# 11-DPLL-2.net
KiCad netlist of a schematic drawn in Altium Designer
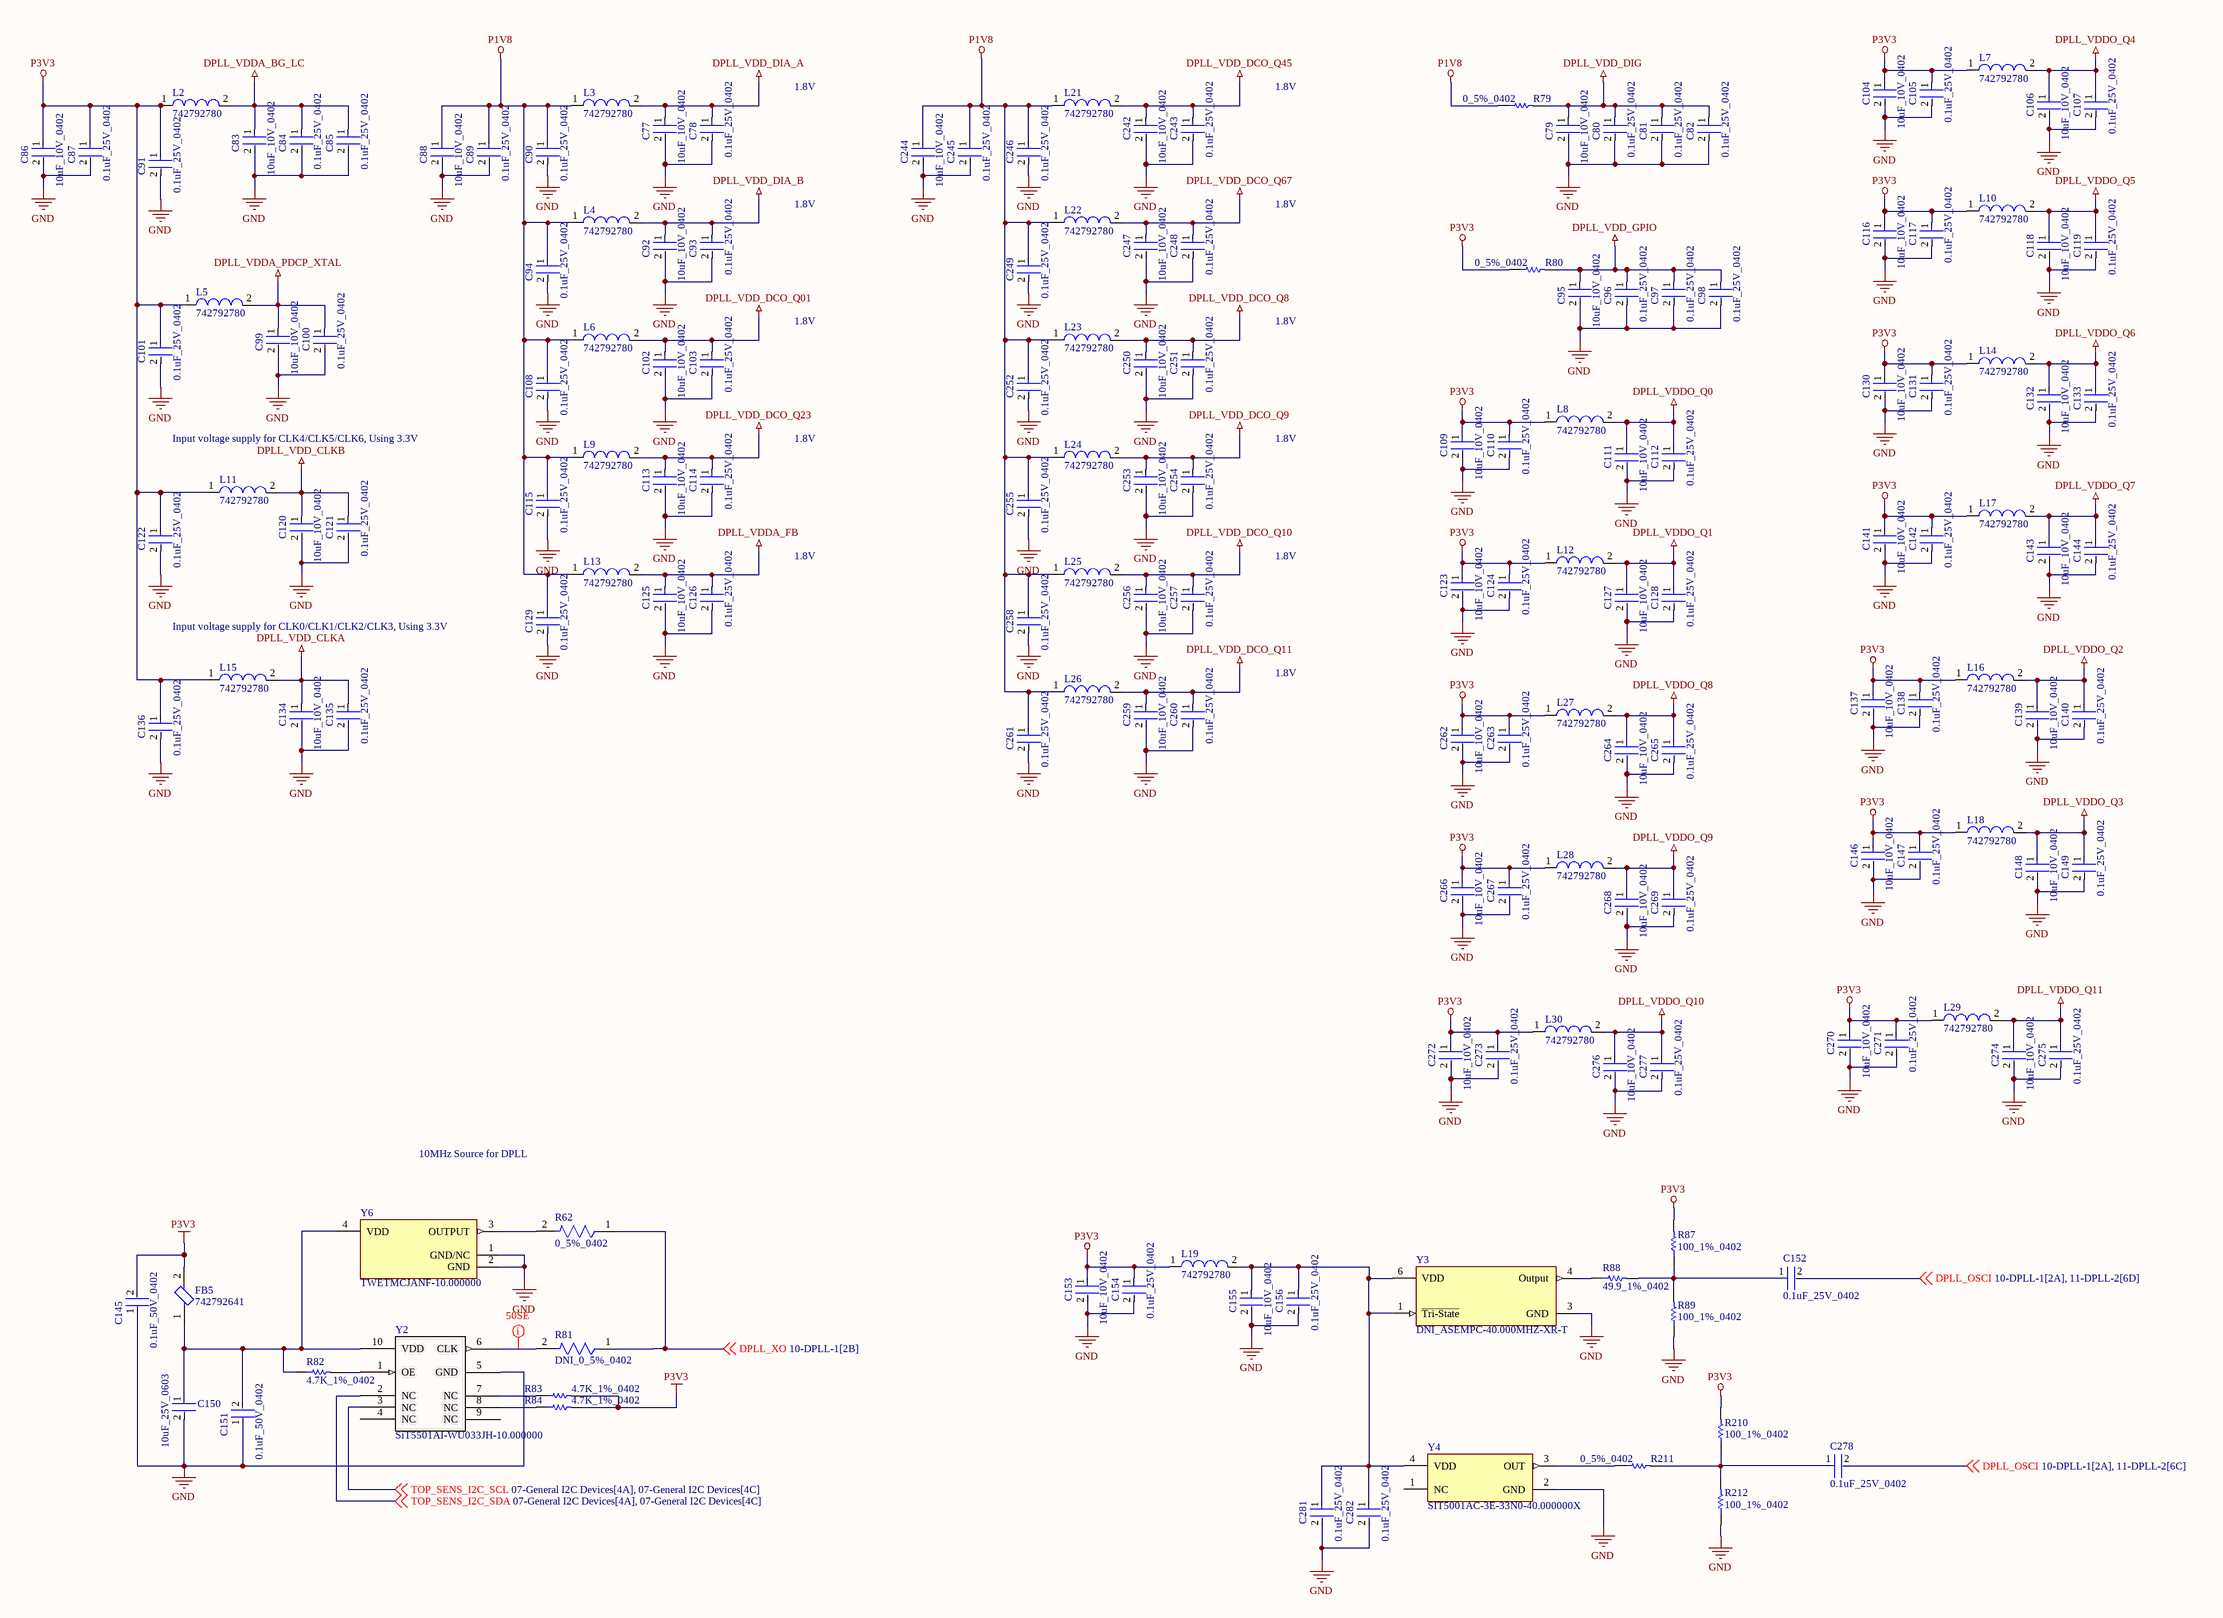
[diagram p0: 11-DPLL-2.SchDoc]

(export (version "E")
  (design (tool "Eeschema 10.0.6"))
  (components
    (comp (ref "C77")
      (value "10uF_10V_0402")
      (footprint "FP-CL05A106MP5NUNC-MFG")
      (description "CAP CER 10UF 10V X5R 0402")
      (fields
        (field (name "OCTOPART") "https://octopart.com/cl05a106mp5nunc-samsung-22457395")
        (field (name "TOLERANCE") "20%")
      )
      (libsource (lib "Altium Content Vault") (part "b4654b650e69147ec39a6b967a45e02"))
    )
    (comp (ref "C78")
      (value "0.1uF_25V_0402")
      (footprint "FP-0402-L_1_0_1-W_0_5_0_1-IPC_C")
      (description "General Purpose Ceramic Capacitor, 0402, 100nF, 10%, X7R, 15%, 25V")
      (fields (field (name "VOLTAGE") "25V") (field (name "TOLERANCE") "10%"))
      (libsource (lib "Altium Content Vault") (part "b4654b650e69147ec39a6b967a45e02"))
    )
    (comp (ref "C79")
      (value "10uF_10V_0402")
      (footprint "FP-CL05A106MP5NUNC-MFG")
      (description "CAP CER 10UF 10V X5R 0402")
      (fields
        (field (name "OCTOPART") "https://octopart.com/cl05a106mp5nunc-samsung-22457395")
        (field (name "TOLERANCE") "20%")
      )
      (libsource (lib "Altium Content Vault") (part "b4654b650e69147ec39a6b967a45e02"))
    )
    (comp (ref "C80")
      (value "0.1uF_25V_0402")
      (footprint "FP-0402-L_1_0_1-W_0_5_0_1-IPC_C")
      (description "General Purpose Ceramic Capacitor, 0402, 100nF, 10%, X7R, 15%, 25V")
      (fields (field (name "VOLTAGE") "25V") (field (name "TOLERANCE") "10%"))
      (libsource (lib "Altium Content Vault") (part "b4654b650e69147ec39a6b967a45e02"))
    )
    (comp (ref "C81")
      (value "0.1uF_25V_0402")
      (footprint "FP-0402-L_1_0_1-W_0_5_0_1-IPC_C")
      (description "General Purpose Ceramic Capacitor, 0402, 100nF, 10%, X7R, 15%, 25V")
      (fields (field (name "VOLTAGE") "25V") (field (name "TOLERANCE") "10%"))
      (libsource (lib "Altium Content Vault") (part "b4654b650e69147ec39a6b967a45e02"))
    )
    (comp (ref "C82")
      (value "0.1uF_25V_0402")
      (footprint "FP-0402-L_1_0_1-W_0_5_0_1-IPC_C")
      (description "General Purpose Ceramic Capacitor, 0402, 100nF, 10%, X7R, 15%, 25V")
      (fields (field (name "VOLTAGE") "25V") (field (name "TOLERANCE") "10%"))
      (libsource (lib "Altium Content Vault") (part "b4654b650e69147ec39a6b967a45e02"))
    )
    (comp (ref "C83")
      (value "10uF_10V_0402")
      (footprint "FP-CL05A106MP5NUNC-MFG")
      (description "CAP CER 10UF 10V X5R 0402")
      (fields
        (field (name "OCTOPART") "https://octopart.com/cl05a106mp5nunc-samsung-22457395")
        (field (name "TOLERANCE") "20%")
      )
      (libsource (lib "Altium Content Vault") (part "b4654b650e69147ec39a6b967a45e02"))
    )
    (comp (ref "C84")
      (value "0.1uF_25V_0402")
      (footprint "FP-0402-L_1_0_1-W_0_5_0_1-IPC_C")
      (description "General Purpose Ceramic Capacitor, 0402, 100nF, 10%, X7R, 15%, 25V")
      (fields (field (name "VOLTAGE") "25V") (field (name "TOLERANCE") "10%"))
      (libsource (lib "Altium Content Vault") (part "b4654b650e69147ec39a6b967a45e02"))
    )
    (comp (ref "C85")
      (value "0.1uF_25V_0402")
      (footprint "FP-0402-L_1_0_1-W_0_5_0_1-IPC_C")
      (description "General Purpose Ceramic Capacitor, 0402, 100nF, 10%, X7R, 15%, 25V")
      (fields (field (name "VOLTAGE") "25V") (field (name "TOLERANCE") "10%"))
      (libsource (lib "Altium Content Vault") (part "b4654b650e69147ec39a6b967a45e02"))
    )
    (comp (ref "C86")
      (value "10uF_10V_0402")
      (footprint "FP-CL05A106MP5NUNC-MFG")
      (description "CAP CER 10UF 10V X5R 0402")
      (fields
        (field (name "OCTOPART") "https://octopart.com/cl05a106mp5nunc-samsung-22457395")
        (field (name "TOLERANCE") "20%")
      )
      (libsource (lib "Altium Content Vault") (part "b4654b650e69147ec39a6b967a45e02"))
    )
    (comp (ref "C87")
      (value "0.1uF_25V_0402")
      (footprint "FP-0402-L_1_0_1-W_0_5_0_1-IPC_C")
      (description "General Purpose Ceramic Capacitor, 0402, 100nF, 10%, X7R, 15%, 25V")
      (fields (field (name "VOLTAGE") "25V") (field (name "TOLERANCE") "10%"))
      (libsource (lib "Altium Content Vault") (part "b4654b650e69147ec39a6b967a45e02"))
    )
    (comp (ref "C88")
      (value "10uF_10V_0402")
      (footprint "FP-CL05A106MP5NUNC-MFG")
      (description "CAP CER 10UF 10V X5R 0402")
      (fields
        (field (name "OCTOPART") "https://octopart.com/cl05a106mp5nunc-samsung-22457395")
        (field (name "TOLERANCE") "20%")
      )
      (libsource (lib "Altium Content Vault") (part "b4654b650e69147ec39a6b967a45e02"))
    )
    (comp (ref "C89")
      (value "0.1uF_25V_0402")
      (footprint "FP-0402-L_1_0_1-W_0_5_0_1-IPC_C")
      (description "General Purpose Ceramic Capacitor, 0402, 100nF, 10%, X7R, 15%, 25V")
      (fields (field (name "VOLTAGE") "25V") (field (name "TOLERANCE") "10%"))
      (libsource (lib "Altium Content Vault") (part "b4654b650e69147ec39a6b967a45e02"))
    )
    (comp (ref "C90")
      (value "0.1uF_25V_0402")
      (footprint "FP-0402-L_1_0_1-W_0_5_0_1-IPC_C")
      (description "General Purpose Ceramic Capacitor, 0402, 100nF, 10%, X7R, 15%, 25V")
      (fields (field (name "VOLTAGE") "25V") (field (name "TOLERANCE") "10%"))
      (libsource (lib "Altium Content Vault") (part "b4654b650e69147ec39a6b967a45e02"))
    )
    (comp (ref "C91")
      (value "0.1uF_25V_0402")
      (footprint "FP-0402-L_1_0_1-W_0_5_0_1-IPC_C")
      (description "General Purpose Ceramic Capacitor, 0402, 100nF, 10%, X7R, 15%, 25V")
      (fields (field (name "VOLTAGE") "25V") (field (name "TOLERANCE") "10%"))
      (libsource (lib "Altium Content Vault") (part "b4654b650e69147ec39a6b967a45e02"))
    )
    (comp (ref "C92")
      (value "10uF_10V_0402")
      (footprint "FP-CL05A106MP5NUNC-MFG")
      (description "CAP CER 10UF 10V X5R 0402")
      (fields
        (field (name "OCTOPART") "https://octopart.com/cl05a106mp5nunc-samsung-22457395")
        (field (name "TOLERANCE") "20%")
      )
      (libsource (lib "Altium Content Vault") (part "b4654b650e69147ec39a6b967a45e02"))
    )
    (comp (ref "C93")
      (value "0.1uF_25V_0402")
      (footprint "FP-0402-L_1_0_1-W_0_5_0_1-IPC_C")
      (description "General Purpose Ceramic Capacitor, 0402, 100nF, 10%, X7R, 15%, 25V")
      (fields (field (name "VOLTAGE") "25V") (field (name "TOLERANCE") "10%"))
      (libsource (lib "Altium Content Vault") (part "b4654b650e69147ec39a6b967a45e02"))
    )
    (comp (ref "C94")
      (value "0.1uF_25V_0402")
      (footprint "FP-0402-L_1_0_1-W_0_5_0_1-IPC_C")
      (description "General Purpose Ceramic Capacitor, 0402, 100nF, 10%, X7R, 15%, 25V")
      (fields (field (name "VOLTAGE") "25V") (field (name "TOLERANCE") "10%"))
      (libsource (lib "Altium Content Vault") (part "b4654b650e69147ec39a6b967a45e02"))
    )
    (comp (ref "C95")
      (value "10uF_10V_0402")
      (footprint "FP-CL05A106MP5NUNC-MFG")
      (description "CAP CER 10UF 10V X5R 0402")
      (fields
        (field (name "OCTOPART") "https://octopart.com/cl05a106mp5nunc-samsung-22457395")
        (field (name "TOLERANCE") "20%")
      )
      (libsource (lib "Altium Content Vault") (part "b4654b650e69147ec39a6b967a45e02"))
    )
    (comp (ref "C96")
      (value "0.1uF_25V_0402")
      (footprint "FP-0402-L_1_0_1-W_0_5_0_1-IPC_C")
      (description "General Purpose Ceramic Capacitor, 0402, 100nF, 10%, X7R, 15%, 25V")
      (fields (field (name "VOLTAGE") "25V") (field (name "TOLERANCE") "10%"))
      (libsource (lib "Altium Content Vault") (part "b4654b650e69147ec39a6b967a45e02"))
    )
    (comp (ref "C97")
      (value "0.1uF_25V_0402")
      (footprint "FP-0402-L_1_0_1-W_0_5_0_1-IPC_C")
      (description "General Purpose Ceramic Capacitor, 0402, 100nF, 10%, X7R, 15%, 25V")
      (fields (field (name "VOLTAGE") "25V") (field (name "TOLERANCE") "10%"))
      (libsource (lib "Altium Content Vault") (part "b4654b650e69147ec39a6b967a45e02"))
    )
    (comp (ref "C98")
      (value "0.1uF_25V_0402")
      (footprint "FP-0402-L_1_0_1-W_0_5_0_1-IPC_C")
      (description "General Purpose Ceramic Capacitor, 0402, 100nF, 10%, X7R, 15%, 25V")
      (fields (field (name "VOLTAGE") "25V") (field (name "TOLERANCE") "10%"))
      (libsource (lib "Altium Content Vault") (part "b4654b650e69147ec39a6b967a45e02"))
    )
    (comp (ref "C99")
      (value "10uF_10V_0402")
      (footprint "FP-CL05A106MP5NUNC-MFG")
      (description "CAP CER 10UF 10V X5R 0402")
      (fields
        (field (name "OCTOPART") "https://octopart.com/cl05a106mp5nunc-samsung-22457395")
        (field (name "TOLERANCE") "20%")
      )
      (libsource (lib "Altium Content Vault") (part "b4654b650e69147ec39a6b967a45e02"))
    )
    (comp (ref "C100")
      (value "0.1uF_25V_0402")
      (footprint "FP-0402-L_1_0_1-W_0_5_0_1-IPC_C")
      (description "General Purpose Ceramic Capacitor, 0402, 100nF, 10%, X7R, 15%, 25V")
      (fields (field (name "VOLTAGE") "25V") (field (name "TOLERANCE") "10%"))
      (libsource (lib "Altium Content Vault") (part "b4654b650e69147ec39a6b967a45e02"))
    )
    (comp (ref "C101")
      (value "0.1uF_25V_0402")
      (footprint "FP-0402-L_1_0_1-W_0_5_0_1-IPC_C")
      (description "General Purpose Ceramic Capacitor, 0402, 100nF, 10%, X7R, 15%, 25V")
      (fields (field (name "VOLTAGE") "25V") (field (name "TOLERANCE") "10%"))
      (libsource (lib "Altium Content Vault") (part "b4654b650e69147ec39a6b967a45e02"))
    )
    (comp (ref "C102")
      (value "10uF_10V_0402")
      (footprint "FP-CL05A106MP5NUNC-MFG")
      (description "CAP CER 10UF 10V X5R 0402")
      (fields
        (field (name "OCTOPART") "https://octopart.com/cl05a106mp5nunc-samsung-22457395")
        (field (name "TOLERANCE") "20%")
      )
      (libsource (lib "Altium Content Vault") (part "b4654b650e69147ec39a6b967a45e02"))
    )
    (comp (ref "C103")
      (value "0.1uF_25V_0402")
      (footprint "FP-0402-L_1_0_1-W_0_5_0_1-IPC_C")
      (description "General Purpose Ceramic Capacitor, 0402, 100nF, 10%, X7R, 15%, 25V")
      (fields (field (name "VOLTAGE") "25V") (field (name "TOLERANCE") "10%"))
      (libsource (lib "Altium Content Vault") (part "b4654b650e69147ec39a6b967a45e02"))
    )
    (comp (ref "C104")
      (value "10uF_10V_0402")
      (footprint "FP-CL05A106MP5NUNC-MFG")
      (description "CAP CER 10UF 10V X5R 0402")
      (fields
        (field (name "OCTOPART") "https://octopart.com/cl05a106mp5nunc-samsung-22457395")
        (field (name "TOLERANCE") "20%")
      )
      (libsource (lib "Altium Content Vault") (part "b4654b650e69147ec39a6b967a45e02"))
    )
    (comp (ref "C105")
      (value "0.1uF_25V_0402")
      (footprint "FP-0402-L_1_0_1-W_0_5_0_1-IPC_C")
      (description "General Purpose Ceramic Capacitor, 0402, 100nF, 10%, X7R, 15%, 25V")
      (fields (field (name "VOLTAGE") "25V") (field (name "TOLERANCE") "10%"))
      (libsource (lib "Altium Content Vault") (part "b4654b650e69147ec39a6b967a45e02"))
    )
    (comp (ref "C106")
      (value "10uF_10V_0402")
      (footprint "FP-CL05A106MP5NUNC-MFG")
      (description "CAP CER 10UF 10V X5R 0402")
      (fields
        (field (name "OCTOPART") "https://octopart.com/cl05a106mp5nunc-samsung-22457395")
        (field (name "TOLERANCE") "20%")
      )
      (libsource (lib "Altium Content Vault") (part "b4654b650e69147ec39a6b967a45e02"))
    )
    (comp (ref "C107")
      (value "0.1uF_25V_0402")
      (footprint "FP-0402-L_1_0_1-W_0_5_0_1-IPC_C")
      (description "General Purpose Ceramic Capacitor, 0402, 100nF, 10%, X7R, 15%, 25V")
      (fields (field (name "VOLTAGE") "25V") (field (name "TOLERANCE") "10%"))
      (libsource (lib "Altium Content Vault") (part "b4654b650e69147ec39a6b967a45e02"))
    )
    (comp (ref "C108")
      (value "0.1uF_25V_0402")
      (footprint "FP-0402-L_1_0_1-W_0_5_0_1-IPC_C")
      (description "General Purpose Ceramic Capacitor, 0402, 100nF, 10%, X7R, 15%, 25V")
      (fields (field (name "VOLTAGE") "25V") (field (name "TOLERANCE") "10%"))
      (libsource (lib "Altium Content Vault") (part "b4654b650e69147ec39a6b967a45e02"))
    )
    (comp (ref "C109")
      (value "10uF_10V_0402")
      (footprint "FP-CL05A106MP5NUNC-MFG")
      (description "CAP CER 10UF 10V X5R 0402")
      (fields
        (field (name "OCTOPART") "https://octopart.com/cl05a106mp5nunc-samsung-22457395")
        (field (name "TOLERANCE") "20%")
      )
      (libsource (lib "Altium Content Vault") (part "b4654b650e69147ec39a6b967a45e02"))
    )
    (comp (ref "C110")
      (value "0.1uF_25V_0402")
      (footprint "FP-0402-L_1_0_1-W_0_5_0_1-IPC_C")
      (description "General Purpose Ceramic Capacitor, 0402, 100nF, 10%, X7R, 15%, 25V")
      (fields (field (name "VOLTAGE") "25V") (field (name "TOLERANCE") "10%"))
      (libsource (lib "Altium Content Vault") (part "b4654b650e69147ec39a6b967a45e02"))
    )
    (comp (ref "C111")
      (value "10uF_10V_0402")
      (footprint "FP-CL05A106MP5NUNC-MFG")
      (description "CAP CER 10UF 10V X5R 0402")
      (fields
        (field (name "OCTOPART") "https://octopart.com/cl05a106mp5nunc-samsung-22457395")
        (field (name "TOLERANCE") "20%")
      )
      (libsource (lib "Altium Content Vault") (part "b4654b650e69147ec39a6b967a45e02"))
    )
    (comp (ref "C112")
      (value "0.1uF_25V_0402")
      (footprint "FP-0402-L_1_0_1-W_0_5_0_1-IPC_C")
      (description "General Purpose Ceramic Capacitor, 0402, 100nF, 10%, X7R, 15%, 25V")
      (fields (field (name "VOLTAGE") "25V") (field (name "TOLERANCE") "10%"))
      (libsource (lib "Altium Content Vault") (part "b4654b650e69147ec39a6b967a45e02"))
    )
    (comp (ref "C113")
      (value "10uF_10V_0402")
      (footprint "FP-CL05A106MP5NUNC-MFG")
      (description "CAP CER 10UF 10V X5R 0402")
      (fields
        (field (name "OCTOPART") "https://octopart.com/cl05a106mp5nunc-samsung-22457395")
        (field (name "TOLERANCE") "20%")
      )
      (libsource (lib "Altium Content Vault") (part "b4654b650e69147ec39a6b967a45e02"))
    )
    (comp (ref "C114")
      (value "0.1uF_25V_0402")
      (footprint "FP-0402-L_1_0_1-W_0_5_0_1-IPC_C")
      (description "General Purpose Ceramic Capacitor, 0402, 100nF, 10%, X7R, 15%, 25V")
      (fields (field (name "VOLTAGE") "25V") (field (name "TOLERANCE") "10%"))
      (libsource (lib "Altium Content Vault") (part "b4654b650e69147ec39a6b967a45e02"))
    )
    (comp (ref "C115")
      (value "0.1uF_25V_0402")
      (footprint "FP-0402-L_1_0_1-W_0_5_0_1-IPC_C")
      (description "General Purpose Ceramic Capacitor, 0402, 100nF, 10%, X7R, 15%, 25V")
      (fields (field (name "VOLTAGE") "25V") (field (name "TOLERANCE") "10%"))
      (libsource (lib "Altium Content Vault") (part "b4654b650e69147ec39a6b967a45e02"))
    )
    (comp (ref "C116")
      (value "10uF_10V_0402")
      (footprint "FP-CL05A106MP5NUNC-MFG")
      (description "CAP CER 10UF 10V X5R 0402")
      (fields
        (field (name "OCTOPART") "https://octopart.com/cl05a106mp5nunc-samsung-22457395")
        (field (name "TOLERANCE") "20%")
      )
      (libsource (lib "Altium Content Vault") (part "b4654b650e69147ec39a6b967a45e02"))
    )
    (comp (ref "C117")
      (value "0.1uF_25V_0402")
      (footprint "FP-0402-L_1_0_1-W_0_5_0_1-IPC_C")
      (description "General Purpose Ceramic Capacitor, 0402, 100nF, 10%, X7R, 15%, 25V")
      (fields (field (name "VOLTAGE") "25V") (field (name "TOLERANCE") "10%"))
      (libsource (lib "Altium Content Vault") (part "b4654b650e69147ec39a6b967a45e02"))
    )
    (comp (ref "C118")
      (value "10uF_10V_0402")
      (footprint "FP-CL05A106MP5NUNC-MFG")
      (description "CAP CER 10UF 10V X5R 0402")
      (fields
        (field (name "OCTOPART") "https://octopart.com/cl05a106mp5nunc-samsung-22457395")
        (field (name "TOLERANCE") "20%")
      )
      (libsource (lib "Altium Content Vault") (part "b4654b650e69147ec39a6b967a45e02"))
    )
    (comp (ref "C119")
      (value "0.1uF_25V_0402")
      (footprint "FP-0402-L_1_0_1-W_0_5_0_1-IPC_C")
      (description "General Purpose Ceramic Capacitor, 0402, 100nF, 10%, X7R, 15%, 25V")
      (fields (field (name "VOLTAGE") "25V") (field (name "TOLERANCE") "10%"))
      (libsource (lib "Altium Content Vault") (part "b4654b650e69147ec39a6b967a45e02"))
    )
    (comp (ref "C120")
      (value "10uF_10V_0402")
      (footprint "FP-CL05A106MP5NUNC-MFG")
      (description "CAP CER 10UF 10V X5R 0402")
      (fields
        (field (name "OCTOPART") "https://octopart.com/cl05a106mp5nunc-samsung-22457395")
        (field (name "TOLERANCE") "20%")
      )
      (libsource (lib "Altium Content Vault") (part "b4654b650e69147ec39a6b967a45e02"))
    )
    (comp (ref "C121")
      (value "0.1uF_25V_0402")
      (footprint "FP-0402-L_1_0_1-W_0_5_0_1-IPC_C")
      (description "General Purpose Ceramic Capacitor, 0402, 100nF, 10%, X7R, 15%, 25V")
      (fields (field (name "VOLTAGE") "25V") (field (name "TOLERANCE") "10%"))
      (libsource (lib "Altium Content Vault") (part "b4654b650e69147ec39a6b967a45e02"))
    )
    (comp (ref "C122")
      (value "0.1uF_25V_0402")
      (footprint "FP-0402-L_1_0_1-W_0_5_0_1-IPC_C")
      (description "General Purpose Ceramic Capacitor, 0402, 100nF, 10%, X7R, 15%, 25V")
      (fields (field (name "VOLTAGE") "25V") (field (name "TOLERANCE") "10%"))
      (libsource (lib "Altium Content Vault") (part "b4654b650e69147ec39a6b967a45e02"))
    )
    (comp (ref "C123")
      (value "10uF_10V_0402")
      (footprint "FP-CL05A106MP5NUNC-MFG")
      (description "CAP CER 10UF 10V X5R 0402")
      (fields
        (field (name "OCTOPART") "https://octopart.com/cl05a106mp5nunc-samsung-22457395")
        (field (name "TOLERANCE") "20%")
      )
      (libsource (lib "Altium Content Vault") (part "b4654b650e69147ec39a6b967a45e02"))
    )
    (comp (ref "C124")
      (value "0.1uF_25V_0402")
      (footprint "FP-0402-L_1_0_1-W_0_5_0_1-IPC_C")
      (description "General Purpose Ceramic Capacitor, 0402, 100nF, 10%, X7R, 15%, 25V")
      (fields (field (name "VOLTAGE") "25V") (field (name "TOLERANCE") "10%"))
      (libsource (lib "Altium Content Vault") (part "b4654b650e69147ec39a6b967a45e02"))
    )
    (comp (ref "C125")
      (value "10uF_10V_0402")
      (footprint "FP-CL05A106MP5NUNC-MFG")
      (description "CAP CER 10UF 10V X5R 0402")
      (fields
        (field (name "OCTOPART") "https://octopart.com/cl05a106mp5nunc-samsung-22457395")
        (field (name "TOLERANCE") "20%")
      )
      (libsource (lib "Altium Content Vault") (part "b4654b650e69147ec39a6b967a45e02"))
    )
    (comp (ref "C126")
      (value "0.1uF_25V_0402")
      (footprint "FP-0402-L_1_0_1-W_0_5_0_1-IPC_C")
      (description "General Purpose Ceramic Capacitor, 0402, 100nF, 10%, X7R, 15%, 25V")
      (fields (field (name "VOLTAGE") "25V") (field (name "TOLERANCE") "10%"))
      (libsource (lib "Altium Content Vault") (part "b4654b650e69147ec39a6b967a45e02"))
    )
    (comp (ref "C127")
      (value "10uF_10V_0402")
      (footprint "FP-CL05A106MP5NUNC-MFG")
      (description "CAP CER 10UF 10V X5R 0402")
      (fields
        (field (name "OCTOPART") "https://octopart.com/cl05a106mp5nunc-samsung-22457395")
        (field (name "TOLERANCE") "20%")
      )
      (libsource (lib "Altium Content Vault") (part "b4654b650e69147ec39a6b967a45e02"))
    )
    (comp (ref "C128")
      (value "0.1uF_25V_0402")
      (footprint "FP-0402-L_1_0_1-W_0_5_0_1-IPC_C")
      (description "General Purpose Ceramic Capacitor, 0402, 100nF, 10%, X7R, 15%, 25V")
      (fields (field (name "VOLTAGE") "25V") (field (name "TOLERANCE") "10%"))
      (libsource (lib "Altium Content Vault") (part "b4654b650e69147ec39a6b967a45e02"))
    )
    (comp (ref "C129")
      (value "0.1uF_25V_0402")
      (footprint "FP-0402-L_1_0_1-W_0_5_0_1-IPC_C")
      (description "General Purpose Ceramic Capacitor, 0402, 100nF, 10%, X7R, 15%, 25V")
      (fields (field (name "VOLTAGE") "25V") (field (name "TOLERANCE") "10%"))
      (libsource (lib "Altium Content Vault") (part "b4654b650e69147ec39a6b967a45e02"))
    )
    (comp (ref "C130")
      (value "10uF_10V_0402")
      (footprint "FP-CL05A106MP5NUNC-MFG")
      (description "CAP CER 10UF 10V X5R 0402")
      (fields
        (field (name "OCTOPART") "https://octopart.com/cl05a106mp5nunc-samsung-22457395")
        (field (name "TOLERANCE") "20%")
      )
      (libsource (lib "Altium Content Vault") (part "b4654b650e69147ec39a6b967a45e02"))
    )
    (comp (ref "C131")
      (value "0.1uF_25V_0402")
      (footprint "FP-0402-L_1_0_1-W_0_5_0_1-IPC_C")
      (description "General Purpose Ceramic Capacitor, 0402, 100nF, 10%, X7R, 15%, 25V")
      (fields (field (name "VOLTAGE") "25V") (field (name "TOLERANCE") "10%"))
      (libsource (lib "Altium Content Vault") (part "b4654b650e69147ec39a6b967a45e02"))
    )
    (comp (ref "C132")
      (value "10uF_10V_0402")
      (footprint "FP-CL05A106MP5NUNC-MFG")
      (description "CAP CER 10UF 10V X5R 0402")
      (fields
        (field (name "OCTOPART") "https://octopart.com/cl05a106mp5nunc-samsung-22457395")
        (field (name "TOLERANCE") "20%")
      )
      (libsource (lib "Altium Content Vault") (part "b4654b650e69147ec39a6b967a45e02"))
    )
    (comp (ref "C133")
      (value "0.1uF_25V_0402")
      (footprint "FP-0402-L_1_0_1-W_0_5_0_1-IPC_C")
      (description "General Purpose Ceramic Capacitor, 0402, 100nF, 10%, X7R, 15%, 25V")
      (fields (field (name "VOLTAGE") "25V") (field (name "TOLERANCE") "10%"))
      (libsource (lib "Altium Content Vault") (part "b4654b650e69147ec39a6b967a45e02"))
    )
    (comp (ref "C134")
      (value "10uF_10V_0402")
      (footprint "FP-CL05A106MP5NUNC-MFG")
      (description "CAP CER 10UF 10V X5R 0402")
      (fields
        (field (name "OCTOPART") "https://octopart.com/cl05a106mp5nunc-samsung-22457395")
        (field (name "TOLERANCE") "20%")
      )
      (libsource (lib "Altium Content Vault") (part "b4654b650e69147ec39a6b967a45e02"))
    )
    (comp (ref "C135")
      (value "0.1uF_25V_0402")
      (footprint "FP-0402-L_1_0_1-W_0_5_0_1-IPC_C")
      (description "General Purpose Ceramic Capacitor, 0402, 100nF, 10%, X7R, 15%, 25V")
      (fields (field (name "VOLTAGE") "25V") (field (name "TOLERANCE") "10%"))
      (libsource (lib "Altium Content Vault") (part "b4654b650e69147ec39a6b967a45e02"))
    )
    (comp (ref "C136")
      (value "0.1uF_25V_0402")
      (footprint "FP-0402-L_1_0_1-W_0_5_0_1-IPC_C")
      (description "General Purpose Ceramic Capacitor, 0402, 100nF, 10%, X7R, 15%, 25V")
      (fields (field (name "VOLTAGE") "25V") (field (name "TOLERANCE") "10%"))
      (libsource (lib "Altium Content Vault") (part "b4654b650e69147ec39a6b967a45e02"))
    )
    (comp (ref "C137")
      (value "10uF_10V_0402")
      (footprint "FP-CL05A106MP5NUNC-MFG")
      (description "CAP CER 10UF 10V X5R 0402")
      (fields
        (field (name "OCTOPART") "https://octopart.com/cl05a106mp5nunc-samsung-22457395")
        (field (name "TOLERANCE") "20%")
      )
      (libsource (lib "Altium Content Vault") (part "b4654b650e69147ec39a6b967a45e02"))
    )
    (comp (ref "C138")
      (value "0.1uF_25V_0402")
      (footprint "FP-0402-L_1_0_1-W_0_5_0_1-IPC_C")
      (description "General Purpose Ceramic Capacitor, 0402, 100nF, 10%, X7R, 15%, 25V")
      (fields (field (name "VOLTAGE") "25V") (field (name "TOLERANCE") "10%"))
      (libsource (lib "Altium Content Vault") (part "b4654b650e69147ec39a6b967a45e02"))
    )
    (comp (ref "C139")
      (value "10uF_10V_0402")
      (footprint "FP-CL05A106MP5NUNC-MFG")
      (description "CAP CER 10UF 10V X5R 0402")
      (fields
        (field (name "OCTOPART") "https://octopart.com/cl05a106mp5nunc-samsung-22457395")
        (field (name "TOLERANCE") "20%")
      )
      (libsource (lib "Altium Content Vault") (part "b4654b650e69147ec39a6b967a45e02"))
    )
    (comp (ref "C140")
      (value "0.1uF_25V_0402")
      (footprint "FP-0402-L_1_0_1-W_0_5_0_1-IPC_C")
      (description "General Purpose Ceramic Capacitor, 0402, 100nF, 10%, X7R, 15%, 25V")
      (fields (field (name "VOLTAGE") "25V") (field (name "TOLERANCE") "10%"))
      (libsource (lib "Altium Content Vault") (part "b4654b650e69147ec39a6b967a45e02"))
    )
    (comp (ref "C141")
      (value "10uF_10V_0402")
      (footprint "FP-CL05A106MP5NUNC-MFG")
      (description "CAP CER 10UF 10V X5R 0402")
      (fields
        (field (name "OCTOPART") "https://octopart.com/cl05a106mp5nunc-samsung-22457395")
        (field (name "TOLERANCE") "20%")
      )
      (libsource (lib "Altium Content Vault") (part "b4654b650e69147ec39a6b967a45e02"))
    )
    (comp (ref "C142")
      (value "0.1uF_25V_0402")
      (footprint "FP-0402-L_1_0_1-W_0_5_0_1-IPC_C")
      (description "General Purpose Ceramic Capacitor, 0402, 100nF, 10%, X7R, 15%, 25V")
      (fields (field (name "VOLTAGE") "25V") (field (name "TOLERANCE") "10%"))
      (libsource (lib "Altium Content Vault") (part "b4654b650e69147ec39a6b967a45e02"))
    )
    (comp (ref "C143")
      (value "10uF_10V_0402")
      (footprint "FP-CL05A106MP5NUNC-MFG")
      (description "CAP CER 10UF 10V X5R 0402")
      (fields
        (field (name "OCTOPART") "https://octopart.com/cl05a106mp5nunc-samsung-22457395")
        (field (name "TOLERANCE") "20%")
      )
      (libsource (lib "Altium Content Vault") (part "b4654b650e69147ec39a6b967a45e02"))
    )
    (comp (ref "C144")
      (value "0.1uF_25V_0402")
      (footprint "FP-0402-L_1_0_1-W_0_5_0_1-IPC_C")
      (description "General Purpose Ceramic Capacitor, 0402, 100nF, 10%, X7R, 15%, 25V")
      (fields (field (name "VOLTAGE") "25V") (field (name "TOLERANCE") "10%"))
      (libsource (lib "Altium Content Vault") (part "b4654b650e69147ec39a6b967a45e02"))
    )
    (comp (ref "C145")
      (value "0.1uF_50V_0402")
      (footprint "FP-C1005-050-0_05-IPC_C")
      (description "Multilayer Ceramic Capacitors 100nF ±10% 50V X7R SMD 0402")
      (fields (field (name "VOLTAGE") "50V") (field (name "TOLERANCE") "10%"))
      (libsource (lib "Altium Content Vault") (part "b4654b650e69147ec39a6b967a45e02"))
    )
    (comp (ref "C146")
      (value "10uF_10V_0402")
      (footprint "FP-CL05A106MP5NUNC-MFG")
      (description "CAP CER 10UF 10V X5R 0402")
      (fields
        (field (name "OCTOPART") "https://octopart.com/cl05a106mp5nunc-samsung-22457395")
        (field (name "TOLERANCE") "20%")
      )
      (libsource (lib "Altium Content Vault") (part "b4654b650e69147ec39a6b967a45e02"))
    )
    (comp (ref "C147")
      (value "0.1uF_25V_0402")
      (footprint "FP-0402-L_1_0_1-W_0_5_0_1-IPC_C")
      (description "General Purpose Ceramic Capacitor, 0402, 100nF, 10%, X7R, 15%, 25V")
      (fields (field (name "VOLTAGE") "25V") (field (name "TOLERANCE") "10%"))
      (libsource (lib "Altium Content Vault") (part "b4654b650e69147ec39a6b967a45e02"))
    )
    (comp (ref "C148")
      (value "10uF_10V_0402")
      (footprint "FP-CL05A106MP5NUNC-MFG")
      (description "CAP CER 10UF 10V X5R 0402")
      (fields
        (field (name "OCTOPART") "https://octopart.com/cl05a106mp5nunc-samsung-22457395")
        (field (name "TOLERANCE") "20%")
      )
      (libsource (lib "Altium Content Vault") (part "b4654b650e69147ec39a6b967a45e02"))
    )
    (comp (ref "C149")
      (value "0.1uF_25V_0402")
      (footprint "FP-0402-L_1_0_1-W_0_5_0_1-IPC_C")
      (description "General Purpose Ceramic Capacitor, 0402, 100nF, 10%, X7R, 15%, 25V")
      (fields (field (name "VOLTAGE") "25V") (field (name "TOLERANCE") "10%"))
      (libsource (lib "Altium Content Vault") (part "b4654b650e69147ec39a6b967a45e02"))
    )
    (comp (ref "C150")
      (value "10uF_25V_0603")
      (footprint "FP-CL10-IPC_C")
      (description "Cap Ceramic 10uF 25V X5R ±20% Pad SMD 0603 +85°C T/R")
      (fields (field (name "TOLERANCE") "20%"))
      (libsource (lib "Altium Content Vault") (part "b4654b650e69147ec39a6b967a45e02"))
    )
    (comp (ref "C151")
      (value "0.1uF_50V_0402")
      (footprint "FP-C1005-050-0_05-IPC_C")
      (description "Multilayer Ceramic Capacitors 100nF ±10% 50V X7R SMD 0402")
      (fields (field (name "VOLTAGE") "50V") (field (name "TOLERANCE") "10%"))
      (libsource (lib "Altium Content Vault") (part "b4654b650e69147ec39a6b967a45e02"))
    )
    (comp (ref "C152")
      (value "0.1uF_25V_0402")
      (footprint "FP-0402-L_1_0_1-W_0_5_0_1-IPC_C")
      (description "General Purpose Ceramic Capacitor, 0402, 100nF, 10%, X7R, 15%, 25V")
      (fields (field (name "VOLTAGE") "25V") (field (name "TOLERANCE") "10%"))
      (libsource (lib "Altium Content Vault") (part "b4654b650e69147ec39a6b967a45e02"))
    )
    (comp (ref "C153")
      (value "10uF_10V_0402")
      (footprint "FP-CL05A106MP5NUNC-MFG")
      (description "CAP CER 10UF 10V X5R 0402")
      (fields
        (field (name "OCTOPART") "https://octopart.com/cl05a106mp5nunc-samsung-22457395")
        (field (name "TOLERANCE") "20%")
      )
      (libsource (lib "Altium Content Vault") (part "b4654b650e69147ec39a6b967a45e02"))
    )
    (comp (ref "C154")
      (value "0.1uF_25V_0402")
      (footprint "FP-0402-L_1_0_1-W_0_5_0_1-IPC_C")
      (description "General Purpose Ceramic Capacitor, 0402, 100nF, 10%, X7R, 15%, 25V")
      (fields (field (name "VOLTAGE") "25V") (field (name "TOLERANCE") "10%"))
      (libsource (lib "Altium Content Vault") (part "b4654b650e69147ec39a6b967a45e02"))
    )
    (comp (ref "C155")
      (value "10uF_10V_0402")
      (footprint "FP-CL05A106MP5NUNC-MFG")
      (description "CAP CER 10UF 10V X5R 0402")
      (fields
        (field (name "OCTOPART") "https://octopart.com/cl05a106mp5nunc-samsung-22457395")
        (field (name "TOLERANCE") "20%")
      )
      (libsource (lib "Altium Content Vault") (part "b4654b650e69147ec39a6b967a45e02"))
    )
    (comp (ref "C156")
      (value "0.1uF_25V_0402")
      (footprint "FP-0402-L_1_0_1-W_0_5_0_1-IPC_C")
      (description "General Purpose Ceramic Capacitor, 0402, 100nF, 10%, X7R, 15%, 25V")
      (fields (field (name "VOLTAGE") "25V") (field (name "TOLERANCE") "10%"))
      (libsource (lib "Altium Content Vault") (part "b4654b650e69147ec39a6b967a45e02"))
    )
    (comp (ref "C242")
      (value "10uF_10V_0402")
      (footprint "FP-CL05A106MP5NUNC-MFG")
      (description "CAP CER 10UF 10V X5R 0402")
      (fields
        (field (name "OCTOPART") "https://octopart.com/cl05a106mp5nunc-samsung-22457395")
        (field (name "TOLERANCE") "20%")
      )
      (libsource (lib "Altium Content Vault") (part "b4654b650e69147ec39a6b967a45e02"))
    )
    (comp (ref "C243")
      (value "0.1uF_25V_0402")
      (footprint "FP-0402-L_1_0_1-W_0_5_0_1-IPC_C")
      (description "General Purpose Ceramic Capacitor, 0402, 100nF, 10%, X7R, 15%, 25V")
      (fields (field (name "VOLTAGE") "25V") (field (name "TOLERANCE") "10%"))
      (libsource (lib "Altium Content Vault") (part "b4654b650e69147ec39a6b967a45e02"))
    )
    (comp (ref "C244")
      (value "10uF_10V_0402")
      (footprint "FP-CL05A106MP5NUNC-MFG")
      (description "CAP CER 10UF 10V X5R 0402")
      (fields
        (field (name "OCTOPART") "https://octopart.com/cl05a106mp5nunc-samsung-22457395")
        (field (name "TOLERANCE") "20%")
      )
      (libsource (lib "Altium Content Vault") (part "b4654b650e69147ec39a6b967a45e02"))
    )
    (comp (ref "C245")
      (value "0.1uF_25V_0402")
      (footprint "FP-0402-L_1_0_1-W_0_5_0_1-IPC_C")
      (description "General Purpose Ceramic Capacitor, 0402, 100nF, 10%, X7R, 15%, 25V")
      (fields (field (name "VOLTAGE") "25V") (field (name "TOLERANCE") "10%"))
      (libsource (lib "Altium Content Vault") (part "b4654b650e69147ec39a6b967a45e02"))
    )
    (comp (ref "C246")
      (value "0.1uF_25V_0402")
      (footprint "FP-0402-L_1_0_1-W_0_5_0_1-IPC_C")
      (description "General Purpose Ceramic Capacitor, 0402, 100nF, 10%, X7R, 15%, 25V")
      (fields (field (name "VOLTAGE") "25V") (field (name "TOLERANCE") "10%"))
      (libsource (lib "Altium Content Vault") (part "b4654b650e69147ec39a6b967a45e02"))
    )
    (comp (ref "C247")
      (value "10uF_10V_0402")
      (footprint "FP-CL05A106MP5NUNC-MFG")
      (description "CAP CER 10UF 10V X5R 0402")
      (fields
        (field (name "OCTOPART") "https://octopart.com/cl05a106mp5nunc-samsung-22457395")
        (field (name "TOLERANCE") "20%")
      )
      (libsource (lib "Altium Content Vault") (part "b4654b650e69147ec39a6b967a45e02"))
    )
    (comp (ref "C248")
      (value "0.1uF_25V_0402")
      (footprint "FP-0402-L_1_0_1-W_0_5_0_1-IPC_C")
      (description "General Purpose Ceramic Capacitor, 0402, 100nF, 10%, X7R, 15%, 25V")
      (fields (field (name "VOLTAGE") "25V") (field (name "TOLERANCE") "10%"))
      (libsource (lib "Altium Content Vault") (part "b4654b650e69147ec39a6b967a45e02"))
    )
    (comp (ref "C249")
      (value "0.1uF_25V_0402")
      (footprint "FP-0402-L_1_0_1-W_0_5_0_1-IPC_C")
      (description "General Purpose Ceramic Capacitor, 0402, 100nF, 10%, X7R, 15%, 25V")
      (fields (field (name "VOLTAGE") "25V") (field (name "TOLERANCE") "10%"))
      (libsource (lib "Altium Content Vault") (part "b4654b650e69147ec39a6b967a45e02"))
    )
    (comp (ref "C250")
      (value "10uF_10V_0402")
      (footprint "FP-CL05A106MP5NUNC-MFG")
      (description "CAP CER 10UF 10V X5R 0402")
      (fields
        (field (name "OCTOPART") "https://octopart.com/cl05a106mp5nunc-samsung-22457395")
        (field (name "TOLERANCE") "20%")
      )
      (libsource (lib "Altium Content Vault") (part "b4654b650e69147ec39a6b967a45e02"))
    )
    (comp (ref "C251")
      (value "0.1uF_25V_0402")
      (footprint "FP-0402-L_1_0_1-W_0_5_0_1-IPC_C")
      (description "General Purpose Ceramic Capacitor, 0402, 100nF, 10%, X7R, 15%, 25V")
      (fields (field (name "VOLTAGE") "25V") (field (name "TOLERANCE") "10%"))
      (libsource (lib "Altium Content Vault") (part "b4654b650e69147ec39a6b967a45e02"))
    )
    (comp (ref "C252")
      (value "0.1uF_25V_0402")
      (footprint "FP-0402-L_1_0_1-W_0_5_0_1-IPC_C")
      (description "General Purpose Ceramic Capacitor, 0402, 100nF, 10%, X7R, 15%, 25V")
      (fields (field (name "VOLTAGE") "25V") (field (name "TOLERANCE") "10%"))
      (libsource (lib "Altium Content Vault") (part "b4654b650e69147ec39a6b967a45e02"))
    )
    (comp (ref "C253")
      (value "10uF_10V_0402")
      (footprint "FP-CL05A106MP5NUNC-MFG")
      (description "CAP CER 10UF 10V X5R 0402")
      (fields
        (field (name "OCTOPART") "https://octopart.com/cl05a106mp5nunc-samsung-22457395")
        (field (name "TOLERANCE") "20%")
      )
      (libsource (lib "Altium Content Vault") (part "b4654b650e69147ec39a6b967a45e02"))
    )
    (comp (ref "C254")
      (value "0.1uF_25V_0402")
      (footprint "FP-0402-L_1_0_1-W_0_5_0_1-IPC_C")
      (description "General Purpose Ceramic Capacitor, 0402, 100nF, 10%, X7R, 15%, 25V")
      (fields (field (name "VOLTAGE") "25V") (field (name "TOLERANCE") "10%"))
      (libsource (lib "Altium Content Vault") (part "b4654b650e69147ec39a6b967a45e02"))
    )
    (comp (ref "C255")
      (value "0.1uF_25V_0402")
      (footprint "FP-0402-L_1_0_1-W_0_5_0_1-IPC_C")
      (description "General Purpose Ceramic Capacitor, 0402, 100nF, 10%, X7R, 15%, 25V")
      (fields (field (name "VOLTAGE") "25V") (field (name "TOLERANCE") "10%"))
      (libsource (lib "Altium Content Vault") (part "b4654b650e69147ec39a6b967a45e02"))
    )
    (comp (ref "C256")
      (value "10uF_10V_0402")
      (footprint "FP-CL05A106MP5NUNC-MFG")
      (description "CAP CER 10UF 10V X5R 0402")
      (fields
        (field (name "OCTOPART") "https://octopart.com/cl05a106mp5nunc-samsung-22457395")
        (field (name "TOLERANCE") "20%")
      )
      (libsource (lib "Altium Content Vault") (part "b4654b650e69147ec39a6b967a45e02"))
    )
    (comp (ref "C257")
      (value "0.1uF_25V_0402")
      (footprint "FP-0402-L_1_0_1-W_0_5_0_1-IPC_C")
      (description "General Purpose Ceramic Capacitor, 0402, 100nF, 10%, X7R, 15%, 25V")
      (fields (field (name "VOLTAGE") "25V") (field (name "TOLERANCE") "10%"))
      (libsource (lib "Altium Content Vault") (part "b4654b650e69147ec39a6b967a45e02"))
    )
    (comp (ref "C258")
      (value "0.1uF_25V_0402")
      (footprint "FP-0402-L_1_0_1-W_0_5_0_1-IPC_C")
      (description "General Purpose Ceramic Capacitor, 0402, 100nF, 10%, X7R, 15%, 25V")
      (fields (field (name "VOLTAGE") "25V") (field (name "TOLERANCE") "10%"))
      (libsource (lib "Altium Content Vault") (part "b4654b650e69147ec39a6b967a45e02"))
    )
    (comp (ref "C259")
      (value "10uF_10V_0402")
      (footprint "FP-CL05A106MP5NUNC-MFG")
      (description "CAP CER 10UF 10V X5R 0402")
      (fields
        (field (name "OCTOPART") "https://octopart.com/cl05a106mp5nunc-samsung-22457395")
        (field (name "TOLERANCE") "20%")
      )
      (libsource (lib "Altium Content Vault") (part "b4654b650e69147ec39a6b967a45e02"))
    )
    (comp (ref "C260")
      (value "0.1uF_25V_0402")
      (footprint "FP-0402-L_1_0_1-W_0_5_0_1-IPC_C")
      (description "General Purpose Ceramic Capacitor, 0402, 100nF, 10%, X7R, 15%, 25V")
      (fields (field (name "VOLTAGE") "25V") (field (name "TOLERANCE") "10%"))
      (libsource (lib "Altium Content Vault") (part "b4654b650e69147ec39a6b967a45e02"))
    )
    (comp (ref "C261")
      (value "0.1uF_25V_0402")
      (footprint "FP-0402-L_1_0_1-W_0_5_0_1-IPC_C")
      (description "General Purpose Ceramic Capacitor, 0402, 100nF, 10%, X7R, 15%, 25V")
      (fields (field (name "VOLTAGE") "25V") (field (name "TOLERANCE") "10%"))
      (libsource (lib "Altium Content Vault") (part "b4654b650e69147ec39a6b967a45e02"))
    )
    (comp (ref "C262")
      (value "10uF_10V_0402")
      (footprint "FP-CL05A106MP5NUNC-MFG")
      (description "CAP CER 10UF 10V X5R 0402")
      (fields
        (field (name "OCTOPART") "https://octopart.com/cl05a106mp5nunc-samsung-22457395")
        (field (name "TOLERANCE") "20%")
      )
      (libsource (lib "Altium Content Vault") (part "b4654b650e69147ec39a6b967a45e02"))
    )
    (comp (ref "C263")
      (value "0.1uF_25V_0402")
      (footprint "FP-0402-L_1_0_1-W_0_5_0_1-IPC_C")
      (description "General Purpose Ceramic Capacitor, 0402, 100nF, 10%, X7R, 15%, 25V")
      (fields (field (name "VOLTAGE") "25V") (field (name "TOLERANCE") "10%"))
      (libsource (lib "Altium Content Vault") (part "b4654b650e69147ec39a6b967a45e02"))
    )
    (comp (ref "C264")
      (value "10uF_10V_0402")
      (footprint "FP-CL05A106MP5NUNC-MFG")
      (description "CAP CER 10UF 10V X5R 0402")
      (fields
        (field (name "OCTOPART") "https://octopart.com/cl05a106mp5nunc-samsung-22457395")
        (field (name "TOLERANCE") "20%")
      )
      (libsource (lib "Altium Content Vault") (part "b4654b650e69147ec39a6b967a45e02"))
    )
    (comp (ref "C265")
      (value "0.1uF_25V_0402")
      (footprint "FP-0402-L_1_0_1-W_0_5_0_1-IPC_C")
      (description "General Purpose Ceramic Capacitor, 0402, 100nF, 10%, X7R, 15%, 25V")
      (fields (field (name "VOLTAGE") "25V") (field (name "TOLERANCE") "10%"))
      (libsource (lib "Altium Content Vault") (part "b4654b650e69147ec39a6b967a45e02"))
    )
    (comp (ref "C266")
      (value "10uF_10V_0402")
      (footprint "FP-CL05A106MP5NUNC-MFG")
      (description "CAP CER 10UF 10V X5R 0402")
      (fields
        (field (name "OCTOPART") "https://octopart.com/cl05a106mp5nunc-samsung-22457395")
        (field (name "TOLERANCE") "20%")
      )
      (libsource (lib "Altium Content Vault") (part "b4654b650e69147ec39a6b967a45e02"))
    )
    (comp (ref "C267")
      (value "0.1uF_25V_0402")
      (footprint "FP-0402-L_1_0_1-W_0_5_0_1-IPC_C")
      (description "General Purpose Ceramic Capacitor, 0402, 100nF, 10%, X7R, 15%, 25V")
      (fields (field (name "VOLTAGE") "25V") (field (name "TOLERANCE") "10%"))
      (libsource (lib "Altium Content Vault") (part "b4654b650e69147ec39a6b967a45e02"))
    )
    (comp (ref "C268")
      (value "10uF_10V_0402")
      (footprint "FP-CL05A106MP5NUNC-MFG")
      (description "CAP CER 10UF 10V X5R 0402")
      (fields
        (field (name "OCTOPART") "https://octopart.com/cl05a106mp5nunc-samsung-22457395")
        (field (name "TOLERANCE") "20%")
      )
      (libsource (lib "Altium Content Vault") (part "b4654b650e69147ec39a6b967a45e02"))
    )
    (comp (ref "C269")
      (value "0.1uF_25V_0402")
      (footprint "FP-0402-L_1_0_1-W_0_5_0_1-IPC_C")
      (description "General Purpose Ceramic Capacitor, 0402, 100nF, 10%, X7R, 15%, 25V")
      (fields (field (name "VOLTAGE") "25V") (field (name "TOLERANCE") "10%"))
      (libsource (lib "Altium Content Vault") (part "b4654b650e69147ec39a6b967a45e02"))
    )
    (comp (ref "C270")
      (value "10uF_10V_0402")
      (footprint "FP-CL05A106MP5NUNC-MFG")
      (description "CAP CER 10UF 10V X5R 0402")
      (fields
        (field (name "OCTOPART") "https://octopart.com/cl05a106mp5nunc-samsung-22457395")
        (field (name "TOLERANCE") "20%")
      )
      (libsource (lib "Altium Content Vault") (part "b4654b650e69147ec39a6b967a45e02"))
    )
    (comp (ref "C271")
      (value "0.1uF_25V_0402")
      (footprint "FP-0402-L_1_0_1-W_0_5_0_1-IPC_C")
      (description "General Purpose Ceramic Capacitor, 0402, 100nF, 10%, X7R, 15%, 25V")
      (fields (field (name "VOLTAGE") "25V") (field (name "TOLERANCE") "10%"))
      (libsource (lib "Altium Content Vault") (part "b4654b650e69147ec39a6b967a45e02"))
    )
    (comp (ref "C272")
      (value "10uF_10V_0402")
      (footprint "FP-CL05A106MP5NUNC-MFG")
      (description "CAP CER 10UF 10V X5R 0402")
      (fields
        (field (name "OCTOPART") "https://octopart.com/cl05a106mp5nunc-samsung-22457395")
        (field (name "TOLERANCE") "20%")
      )
      (libsource (lib "Altium Content Vault") (part "b4654b650e69147ec39a6b967a45e02"))
    )
    (comp (ref "C273")
      (value "0.1uF_25V_0402")
      (footprint "FP-0402-L_1_0_1-W_0_5_0_1-IPC_C")
      (description "General Purpose Ceramic Capacitor, 0402, 100nF, 10%, X7R, 15%, 25V")
      (fields (field (name "VOLTAGE") "25V") (field (name "TOLERANCE") "10%"))
      (libsource (lib "Altium Content Vault") (part "b4654b650e69147ec39a6b967a45e02"))
    )
    (comp (ref "C274")
      (value "10uF_10V_0402")
      (footprint "FP-CL05A106MP5NUNC-MFG")
      (description "CAP CER 10UF 10V X5R 0402")
      (fields
        (field (name "OCTOPART") "https://octopart.com/cl05a106mp5nunc-samsung-22457395")
        (field (name "TOLERANCE") "20%")
      )
      (libsource (lib "Altium Content Vault") (part "b4654b650e69147ec39a6b967a45e02"))
    )
    (comp (ref "C275")
      (value "0.1uF_25V_0402")
      (footprint "FP-0402-L_1_0_1-W_0_5_0_1-IPC_C")
      (description "General Purpose Ceramic Capacitor, 0402, 100nF, 10%, X7R, 15%, 25V")
      (fields (field (name "VOLTAGE") "25V") (field (name "TOLERANCE") "10%"))
      (libsource (lib "Altium Content Vault") (part "b4654b650e69147ec39a6b967a45e02"))
    )
    (comp (ref "C276")
      (value "10uF_10V_0402")
      (footprint "FP-CL05A106MP5NUNC-MFG")
      (description "CAP CER 10UF 10V X5R 0402")
      (fields
        (field (name "OCTOPART") "https://octopart.com/cl05a106mp5nunc-samsung-22457395")
        (field (name "TOLERANCE") "20%")
      )
      (libsource (lib "Altium Content Vault") (part "b4654b650e69147ec39a6b967a45e02"))
    )
    (comp (ref "C277")
      (value "0.1uF_25V_0402")
      (footprint "FP-0402-L_1_0_1-W_0_5_0_1-IPC_C")
      (description "General Purpose Ceramic Capacitor, 0402, 100nF, 10%, X7R, 15%, 25V")
      (fields (field (name "VOLTAGE") "25V") (field (name "TOLERANCE") "10%"))
      (libsource (lib "Altium Content Vault") (part "b4654b650e69147ec39a6b967a45e02"))
    )
    (comp (ref "C278")
      (value "0.1uF_25V_0402")
      (footprint "FP-0402-L_1_0_1-W_0_5_0_1-IPC_C")
      (description "General Purpose Ceramic Capacitor, 0402, 100nF, 10%, X7R, 15%, 25V")
      (fields (field (name "VOLTAGE") "25V") (field (name "TOLERANCE") "10%"))
      (libsource (lib "Altium Content Vault") (part "b4654b650e69147ec39a6b967a45e02"))
    )
    (comp (ref "C281")
      (value "0.1uF_25V_0402")
      (footprint "FP-0402-L_1_0_1-W_0_5_0_1-IPC_C")
      (description "General Purpose Ceramic Capacitor, 0402, 100nF, 10%, X7R, 15%, 25V")
      (fields (field (name "VOLTAGE") "25V") (field (name "TOLERANCE") "10%"))
      (libsource (lib "Altium Content Vault") (part "b4654b650e69147ec39a6b967a45e02"))
    )
    (comp (ref "C282")
      (value "0.1uF_25V_0402")
      (footprint "FP-0402-L_1_0_1-W_0_5_0_1-IPC_C")
      (description "General Purpose Ceramic Capacitor, 0402, 100nF, 10%, X7R, 15%, 25V")
      (fields (field (name "VOLTAGE") "25V") (field (name "TOLERANCE") "10%"))
      (libsource (lib "Altium Content Vault") (part "b4654b650e69147ec39a6b967a45e02"))
    )
    (comp (ref "FB5")
      (value "742792641")
      (footprint "FP-742792641-MFG")
      (description "FERRITE BEAD 300 OHM 0603 1LN")
      (fields (field (name "TOLERANCE") "25%"))
      (libsource (lib "Altium Content Vault") (part "5f30dd21d616792df468990f7003faa"))
    )
    (comp (ref "L2")
      (value "742792780")
      (footprint "SMD-0402")
      (description "SMD EMI Suppression Ferrite Bead WE-CBF, Z = 220 Ohm")
      (libsource (lib "Altium Content Vault") (part "PAS-IND-INDUCTOR-2"))
    )
    (comp (ref "L3")
      (value "742792780")
      (footprint "SMD-0402")
      (description "SMD EMI Suppression Ferrite Bead WE-CBF, Z = 220 Ohm")
      (libsource (lib "Altium Content Vault") (part "PAS-IND-INDUCTOR-2"))
    )
    (comp (ref "L4")
      (value "742792780")
      (footprint "SMD-0402")
      (description "SMD EMI Suppression Ferrite Bead WE-CBF, Z = 220 Ohm")
      (libsource (lib "Altium Content Vault") (part "PAS-IND-INDUCTOR-2"))
    )
    (comp (ref "L5")
      (value "742792780")
      (footprint "SMD-0402")
      (description "SMD EMI Suppression Ferrite Bead WE-CBF, Z = 220 Ohm")
      (libsource (lib "Altium Content Vault") (part "PAS-IND-INDUCTOR-2"))
    )
    (comp (ref "L6")
      (value "742792780")
      (footprint "SMD-0402")
      (description "SMD EMI Suppression Ferrite Bead WE-CBF, Z = 220 Ohm")
      (libsource (lib "Altium Content Vault") (part "PAS-IND-INDUCTOR-2"))
    )
    (comp (ref "L7")
      (value "742792780")
      (footprint "SMD-0402")
      (description "SMD EMI Suppression Ferrite Bead WE-CBF, Z = 220 Ohm")
      (libsource (lib "Altium Content Vault") (part "PAS-IND-INDUCTOR-2"))
    )
    (comp (ref "L8")
      (value "742792780")
      (footprint "SMD-0402")
      (description "SMD EMI Suppression Ferrite Bead WE-CBF, Z = 220 Ohm")
      (libsource (lib "Altium Content Vault") (part "PAS-IND-INDUCTOR-2"))
    )
    (comp (ref "L9")
      (value "742792780")
      (footprint "SMD-0402")
      (description "SMD EMI Suppression Ferrite Bead WE-CBF, Z = 220 Ohm")
      (libsource (lib "Altium Content Vault") (part "PAS-IND-INDUCTOR-2"))
    )
    (comp (ref "L10")
      (value "742792780")
      (footprint "SMD-0402")
      (description "SMD EMI Suppression Ferrite Bead WE-CBF, Z = 220 Ohm")
      (libsource (lib "Altium Content Vault") (part "PAS-IND-INDUCTOR-2"))
    )
    (comp (ref "L11")
      (value "742792780")
      (footprint "SMD-0402")
      (description "SMD EMI Suppression Ferrite Bead WE-CBF, Z = 220 Ohm")
      (libsource (lib "Altium Content Vault") (part "PAS-IND-INDUCTOR-2"))
    )
    (comp (ref "L12")
      (value "742792780")
      (footprint "SMD-0402")
      (description "SMD EMI Suppression Ferrite Bead WE-CBF, Z = 220 Ohm")
      (libsource (lib "Altium Content Vault") (part "PAS-IND-INDUCTOR-2"))
    )
    (comp (ref "L13")
      (value "742792780")
      (footprint "SMD-0402")
      (description "SMD EMI Suppression Ferrite Bead WE-CBF, Z = 220 Ohm")
      (libsource (lib "Altium Content Vault") (part "PAS-IND-INDUCTOR-2"))
    )
    (comp (ref "L14")
      (value "742792780")
      (footprint "SMD-0402")
      (description "SMD EMI Suppression Ferrite Bead WE-CBF, Z = 220 Ohm")
      (libsource (lib "Altium Content Vault") (part "PAS-IND-INDUCTOR-2"))
    )
    (comp (ref "L15")
      (value "742792780")
      (footprint "SMD-0402")
      (description "SMD EMI Suppression Ferrite Bead WE-CBF, Z = 220 Ohm")
      (libsource (lib "Altium Content Vault") (part "PAS-IND-INDUCTOR-2"))
    )
    (comp (ref "L16")
      (value "742792780")
      (footprint "SMD-0402")
      (description "SMD EMI Suppression Ferrite Bead WE-CBF, Z = 220 Ohm")
      (libsource (lib "Altium Content Vault") (part "PAS-IND-INDUCTOR-2"))
    )
    (comp (ref "L17")
      (value "742792780")
      (footprint "SMD-0402")
      (description "SMD EMI Suppression Ferrite Bead WE-CBF, Z = 220 Ohm")
      (libsource (lib "Altium Content Vault") (part "PAS-IND-INDUCTOR-2"))
    )
    (comp (ref "L18")
      (value "742792780")
      (footprint "SMD-0402")
      (description "SMD EMI Suppression Ferrite Bead WE-CBF, Z = 220 Ohm")
      (libsource (lib "Altium Content Vault") (part "PAS-IND-INDUCTOR-2"))
    )
    (comp (ref "L19")
      (value "742792780")
      (footprint "SMD-0402")
      (description "SMD EMI Suppression Ferrite Bead WE-CBF, Z = 220 Ohm")
      (libsource (lib "Altium Content Vault") (part "PAS-IND-INDUCTOR-2"))
    )
    (comp (ref "L21")
      (value "742792780")
      (footprint "SMD-0402")
      (description "SMD EMI Suppression Ferrite Bead WE-CBF, Z = 220 Ohm")
      (libsource (lib "Altium Content Vault") (part "PAS-IND-INDUCTOR-2"))
    )
    (comp (ref "L22")
      (value "742792780")
      (footprint "SMD-0402")
      (description "SMD EMI Suppression Ferrite Bead WE-CBF, Z = 220 Ohm")
      (libsource (lib "Altium Content Vault") (part "PAS-IND-INDUCTOR-2"))
    )
    (comp (ref "L23")
      (value "742792780")
      (footprint "SMD-0402")
      (description "SMD EMI Suppression Ferrite Bead WE-CBF, Z = 220 Ohm")
      (libsource (lib "Altium Content Vault") (part "PAS-IND-INDUCTOR-2"))
    )
    (comp (ref "L24")
      (value "742792780")
      (footprint "SMD-0402")
      (description "SMD EMI Suppression Ferrite Bead WE-CBF, Z = 220 Ohm")
      (libsource (lib "Altium Content Vault") (part "PAS-IND-INDUCTOR-2"))
    )
    (comp (ref "L25")
      (value "742792780")
      (footprint "SMD-0402")
      (description "SMD EMI Suppression Ferrite Bead WE-CBF, Z = 220 Ohm")
      (libsource (lib "Altium Content Vault") (part "PAS-IND-INDUCTOR-2"))
    )
    (comp (ref "L26")
      (value "742792780")
      (footprint "SMD-0402")
      (description "SMD EMI Suppression Ferrite Bead WE-CBF, Z = 220 Ohm")
      (libsource (lib "Altium Content Vault") (part "PAS-IND-INDUCTOR-2"))
    )
    (comp (ref "L27")
      (value "742792780")
      (footprint "SMD-0402")
      (description "SMD EMI Suppression Ferrite Bead WE-CBF, Z = 220 Ohm")
      (libsource (lib "Altium Content Vault") (part "PAS-IND-INDUCTOR-2"))
    )
    (comp (ref "L28")
      (value "742792780")
      (footprint "SMD-0402")
      (description "SMD EMI Suppression Ferrite Bead WE-CBF, Z = 220 Ohm")
      (libsource (lib "Altium Content Vault") (part "PAS-IND-INDUCTOR-2"))
    )
    (comp (ref "L29")
      (value "742792780")
      (footprint "SMD-0402")
      (description "SMD EMI Suppression Ferrite Bead WE-CBF, Z = 220 Ohm")
      (libsource (lib "Altium Content Vault") (part "PAS-IND-INDUCTOR-2"))
    )
    (comp (ref "L30")
      (value "742792780")
      (footprint "SMD-0402")
      (description "SMD EMI Suppression Ferrite Bead WE-CBF, Z = 220 Ohm")
      (libsource (lib "Altium Content Vault") (part "PAS-IND-INDUCTOR-2"))
    )
    (comp (ref "R62")
      (value "0_5%_0402")
      (footprint "FP-AC0402-0_37-IPC_B")
      (description "RESISTOR 0402 JUMPER ZERO OHM")
      (fields (field (name "TOLERANCE") "1%"))
      (libsource (lib "Altium Content Vault") (part "1029c3af85768c4190bb7ad29bc67b5"))
    )
    (comp (ref "R79")
      (value "0_5%_0402")
      (footprint "RESC1005X40X25LL10T10")
      (fields (field (name "MANUFACTURER") "KOA Speer") (field (name "PART NUMBER") "RK73Z1ETTP"))
      (libsource (lib "Altium Content Vault") (part "RES"))
    )
    (comp (ref "R80")
      (value "0_5%_0402")
      (footprint "RESC1005X40X25LL10T10")
      (fields (field (name "MANUFACTURER") "KOA Speer") (field (name "PART NUMBER") "RK73Z1ETTP"))
      (libsource (lib "Altium Content Vault") (part "RES"))
    )
    (comp (ref "R81")
      (value "DNI_0_5%_0402")
      (footprint "FP-AC0402-0_37-IPC_B")
      (description "RESISTOR 0402 JUMPER ZERO OHM")
      (fields (field (name "TOLERANCE") "1%"))
      (libsource (lib "Altium Content Vault") (part "1029c3af85768c4190bb7ad29bc67b5"))
    )
    (comp (ref "R82")
      (value "4.7K_1%_0402")
      (footprint "RESC1005X40X25NL10T10")
      (fields (field (name "MANUFACTURER") "Bourns") (field (name "PART NUMBER") "CR0402-FX-4701GLF"))
      (libsource (lib "Altium Content Vault") (part "RES"))
    )
    (comp (ref "R83")
      (value "4.7K_1%_0402")
      (footprint "RESC1005X40X25NL10T10")
      (fields (field (name "MANUFACTURER") "Bourns") (field (name "PART NUMBER") "CR0402-FX-4701GLF"))
      (libsource (lib "Altium Content Vault") (part "RES"))
    )
    (comp (ref "R84")
      (value "4.7K_1%_0402")
      (footprint "RESC1005X40X25NL10T10")
      (fields (field (name "MANUFACTURER") "Bourns") (field (name "PART NUMBER") "CR0402-FX-4701GLF"))
      (libsource (lib "Altium Content Vault") (part "RES"))
    )
    (comp (ref "R87")
      (value "100_1%_0402")
      (footprint "RESC1005X40X25ML05T10")
      (fields (field (name "PART NUMBER") "ERJ-U02F1000X") (field (name "MANUFACTURER") "Panasonic"))
      (libsource (lib "Altium Content Vault") (part "RES"))
    )
    (comp (ref "R88")
      (value "49.9_1%_0402")
      (footprint "RESC1005X40X25NL10T10")
      (fields (field (name "PART NUMBER") "RK73H1ETTP49R9F") (field (name "MANUFACTURER") "KOA Speer"))
      (libsource (lib "Altium Content Vault") (part "RES"))
    )
    (comp (ref "R89")
      (value "100_1%_0402")
      (footprint "RESC1005X40X25ML05T10")
      (fields (field (name "PART NUMBER") "ERJ-U02F1000X") (field (name "MANUFACTURER") "Panasonic"))
      (libsource (lib "Altium Content Vault") (part "RES"))
    )
    (comp (ref "R210")
      (value "100_1%_0402")
      (footprint "RESC1005X40X25ML05T10")
      (fields (field (name "PART NUMBER") "ERJ-U02F1000X") (field (name "MANUFACTURER") "Panasonic"))
      (libsource (lib "Altium Content Vault") (part "RES"))
    )
    (comp (ref "R211")
      (value "0_5%_0402")
      (footprint "RESC1005X40X25LL10T10")
      (fields (field (name "MANUFACTURER") "KOA Speer") (field (name "PART NUMBER") "RK73Z1ETTP"))
      (libsource (lib "Altium Content Vault") (part "RES"))
    )
    (comp (ref "R212")
      (value "100_1%_0402")
      (footprint "RESC1005X40X25ML05T10")
      (fields (field (name "PART NUMBER") "ERJ-U02F1000X") (field (name "MANUFACTURER") "Panasonic"))
      (libsource (lib "Altium Content Vault") (part "RES"))
    )
    (comp (ref "Y2")
      (value "SiTime_SiT5501AC-WU-33E0-10T")
      (footprint "SITIME_SPL-086-CQFN-010-C07050_REV_DRAFT")
      (description "OSC, MEMS, STRATUM 3E, 10.000MHZ, 10PPB STAB, LVCMOS, 3.3V, O/P EN, 7.0X5.0X2.2MM, CQFN-10")
      (fields
        (field (name "MANUFACTURER PART NUMBER") "SiT5501AI-WU033JH-10.000000")
        (field (name "MANUFACTURER") "SiTime")
      )
      (libsource (lib "OCXO_DaughterCard") (part "CMP-OSC-00029-2"))
    )
    (comp (ref "Y3")
      (value "DNI_ASEMPC-40.000MHZ-XR-T")
      (footprint "FP-ASEMP-CMOS-MFG")
      (description "MEMS Oscillator 40MHz ±25ppm CMOS 2.25V~3.6V 6-SMD 3.2mm x 2.5mm")
      (libsource (lib "Altium Content Vault") (part "9526c112e3a98a1af86e8f4e974a861"))
    )
    (comp (ref "Y4")
      (value "SIT5001AC-3E-33N0-40.000000X")
      (footprint "FP-SiT5001-3-MFG")
      (description "MEMS OSC TCXO 40.0000MHZ LVCMOS")
      (libsource (lib "Altium Content Vault") (part "f2b4964c30f19ad016f2c5313c7e3e3"))
    )
    (comp (ref "Y6")
      (value "TWETMCJANF-10.000000")
      (footprint "FP-TWETMCJANF-10_000000-MFG")
      (description "10MHz TCXO CMOS Oscillator 3.3V  4-SMD, No Lead")
      (fields (field (name "OCTOPART") "https://octopart.com/twetmcjanf-10.000000-taitien-75080612"))
      (libsource (lib "Altium Content Vault") (part "cad4c3239b6ef19b17a0f879cedd8e8"))
    )
  )
  (nets
    (net (code "1") (name "DPLL_OSCI") (class "Default")
      (node (ref "C152") (pin "2") (pinfunction "2_2") (pintype "passive"))
      (node (ref "C278") (pin "2") (pinfunction "2_2") (pintype "passive"))
    )
    (net (code "2") (name "DPLL_VDDA_BG_LC") (class "Default")
      (node (ref "C83") (pin "1") (pinfunction "1_1") (pintype "passive"))
      (node (ref "C84") (pin "1") (pinfunction "1_1") (pintype "passive"))
      (node (ref "C85") (pin "1") (pinfunction "1_1") (pintype "passive"))
      (node (ref "L2") (pin "2") (pinfunction "2_2") (pintype "passive"))
    )
    (net (code "3") (name "DPLL_VDDA_FB") (class "Default")
      (node (ref "C125") (pin "1") (pinfunction "1_1") (pintype "passive"))
      (node (ref "C126") (pin "1") (pinfunction "1_1") (pintype "passive"))
      (node (ref "L13") (pin "2") (pinfunction "2_2") (pintype "passive"))
    )
    (net (code "4") (name "DPLL_VDDA_PDCP_XTAL") (class "Default")
      (node (ref "C100") (pin "1") (pinfunction "1_1") (pintype "passive"))
      (node (ref "C99") (pin "1") (pinfunction "1_1") (pintype "passive"))
      (node (ref "L5") (pin "2") (pinfunction "2_2") (pintype "passive"))
    )
    (net (code "5") (name "DPLL_VDDO_Q0") (class "Default")
      (node (ref "C111") (pin "1") (pinfunction "1_1") (pintype "passive"))
      (node (ref "C112") (pin "1") (pinfunction "1_1") (pintype "passive"))
      (node (ref "L8") (pin "2") (pinfunction "2_2") (pintype "passive"))
    )
    (net (code "6") (name "DPLL_VDDO_Q1") (class "Default")
      (node (ref "C127") (pin "1") (pinfunction "1_1") (pintype "passive"))
      (node (ref "C128") (pin "1") (pinfunction "1_1") (pintype "passive"))
      (node (ref "L12") (pin "2") (pinfunction "2_2") (pintype "passive"))
    )
    (net (code "7") (name "DPLL_VDDO_Q2") (class "Default")
      (node (ref "C139") (pin "1") (pinfunction "1_1") (pintype "passive"))
      (node (ref "C140") (pin "1") (pinfunction "1_1") (pintype "passive"))
      (node (ref "L16") (pin "2") (pinfunction "2_2") (pintype "passive"))
    )
    (net (code "8") (name "DPLL_VDDO_Q3") (class "Default")
      (node (ref "C148") (pin "1") (pinfunction "1_1") (pintype "passive"))
      (node (ref "C149") (pin "1") (pinfunction "1_1") (pintype "passive"))
      (node (ref "L18") (pin "2") (pinfunction "2_2") (pintype "passive"))
    )
    (net (code "9") (name "DPLL_VDDO_Q4") (class "Default")
      (node (ref "C106") (pin "1") (pinfunction "1_1") (pintype "passive"))
      (node (ref "C107") (pin "1") (pinfunction "1_1") (pintype "passive"))
      (node (ref "L7") (pin "2") (pinfunction "2_2") (pintype "passive"))
    )
    (net (code "10") (name "DPLL_VDDO_Q5") (class "Default")
      (node (ref "C118") (pin "1") (pinfunction "1_1") (pintype "passive"))
      (node (ref "C119") (pin "1") (pinfunction "1_1") (pintype "passive"))
      (node (ref "L10") (pin "2") (pinfunction "2_2") (pintype "passive"))
    )
    (net (code "11") (name "DPLL_VDDO_Q6") (class "Default")
      (node (ref "C132") (pin "1") (pinfunction "1_1") (pintype "passive"))
      (node (ref "C133") (pin "1") (pinfunction "1_1") (pintype "passive"))
      (node (ref "L14") (pin "2") (pinfunction "2_2") (pintype "passive"))
    )
    (net (code "12") (name "DPLL_VDDO_Q7") (class "Default")
      (node (ref "C143") (pin "1") (pinfunction "1_1") (pintype "passive"))
      (node (ref "C144") (pin "1") (pinfunction "1_1") (pintype "passive"))
      (node (ref "L17") (pin "2") (pinfunction "2_2") (pintype "passive"))
    )
    (net (code "13") (name "DPLL_VDDO_Q8") (class "Default")
      (node (ref "C264") (pin "1") (pinfunction "1_1") (pintype "passive"))
      (node (ref "C265") (pin "1") (pinfunction "1_1") (pintype "passive"))
      (node (ref "L27") (pin "2") (pinfunction "2_2") (pintype "passive"))
    )
    (net (code "14") (name "DPLL_VDDO_Q9") (class "Default")
      (node (ref "C268") (pin "1") (pinfunction "1_1") (pintype "passive"))
      (node (ref "C269") (pin "1") (pinfunction "1_1") (pintype "passive"))
      (node (ref "L28") (pin "2") (pinfunction "2_2") (pintype "passive"))
    )
    (net (code "15") (name "DPLL_VDDO_Q10") (class "Default")
      (node (ref "C276") (pin "1") (pinfunction "1_1") (pintype "passive"))
      (node (ref "C277") (pin "1") (pinfunction "1_1") (pintype "passive"))
      (node (ref "L30") (pin "2") (pinfunction "2_2") (pintype "passive"))
    )
    (net (code "16") (name "DPLL_VDDO_Q11") (class "Default")
      (node (ref "C274") (pin "1") (pinfunction "1_1") (pintype "passive"))
      (node (ref "C275") (pin "1") (pinfunction "1_1") (pintype "passive"))
      (node (ref "L29") (pin "2") (pinfunction "2_2") (pintype "passive"))
    )
    (net (code "17") (name "DPLL_VDD_CLKA") (class "Default")
      (node (ref "C134") (pin "1") (pinfunction "1_1") (pintype "passive"))
      (node (ref "C135") (pin "1") (pinfunction "1_1") (pintype "passive"))
      (node (ref "L15") (pin "2") (pinfunction "2_2") (pintype "passive"))
    )
    (net (code "18") (name "DPLL_VDD_CLKB") (class "Default")
      (node (ref "C120") (pin "1") (pinfunction "1_1") (pintype "passive"))
      (node (ref "C121") (pin "1") (pinfunction "1_1") (pintype "passive"))
      (node (ref "L11") (pin "2") (pinfunction "2_2") (pintype "passive"))
    )
    (net (code "19") (name "DPLL_VDD_DCO_Q01") (class "Default")
      (node (ref "C102") (pin "1") (pinfunction "1_1") (pintype "passive"))
      (node (ref "C103") (pin "1") (pinfunction "1_1") (pintype "passive"))
      (node (ref "L6") (pin "2") (pinfunction "2_2") (pintype "passive"))
    )
    (net (code "20") (name "DPLL_VDD_DCO_Q8") (class "Default")
      (node (ref "C250") (pin "1") (pinfunction "1_1") (pintype "passive"))
      (node (ref "C251") (pin "1") (pinfunction "1_1") (pintype "passive"))
      (node (ref "L23") (pin "2") (pinfunction "2_2") (pintype "passive"))
    )
    (net (code "21") (name "DPLL_VDD_DCO_Q9") (class "Default")
      (node (ref "C253") (pin "1") (pinfunction "1_1") (pintype "passive"))
      (node (ref "C254") (pin "1") (pinfunction "1_1") (pintype "passive"))
      (node (ref "L24") (pin "2") (pinfunction "2_2") (pintype "passive"))
    )
    (net (code "22") (name "DPLL_VDD_DCO_Q10") (class "Default")
      (node (ref "C256") (pin "1") (pinfunction "1_1") (pintype "passive"))
      (node (ref "C257") (pin "1") (pinfunction "1_1") (pintype "passive"))
      (node (ref "L25") (pin "2") (pinfunction "2_2") (pintype "passive"))
    )
    (net (code "23") (name "DPLL_VDD_DCO_Q11") (class "Default")
      (node (ref "C259") (pin "1") (pinfunction "1_1") (pintype "passive"))
      (node (ref "C260") (pin "1") (pinfunction "1_1") (pintype "passive"))
      (node (ref "L26") (pin "2") (pinfunction "2_2") (pintype "passive"))
    )
    (net (code "24") (name "DPLL_VDD_DCO_Q23") (class "Default")
      (node (ref "C113") (pin "1") (pinfunction "1_1") (pintype "passive"))
      (node (ref "C114") (pin "1") (pinfunction "1_1") (pintype "passive"))
      (node (ref "L9") (pin "2") (pinfunction "2_2") (pintype "passive"))
    )
    (net (code "25") (name "DPLL_VDD_DCO_Q45") (class "Default")
      (node (ref "C242") (pin "1") (pinfunction "1_1") (pintype "passive"))
      (node (ref "C243") (pin "1") (pinfunction "1_1") (pintype "passive"))
      (node (ref "L21") (pin "2") (pinfunction "2_2") (pintype "passive"))
    )
    (net (code "26") (name "DPLL_VDD_DCO_Q67") (class "Default")
      (node (ref "C247") (pin "1") (pinfunction "1_1") (pintype "passive"))
      (node (ref "C248") (pin "1") (pinfunction "1_1") (pintype "passive"))
      (node (ref "L22") (pin "2") (pinfunction "2_2") (pintype "passive"))
    )
    (net (code "27") (name "DPLL_VDD_DIA_A") (class "Default")
      (node (ref "C77") (pin "1") (pinfunction "1_1") (pintype "passive"))
      (node (ref "C78") (pin "1") (pinfunction "1_1") (pintype "passive"))
      (node (ref "L3") (pin "2") (pinfunction "2_2") (pintype "passive"))
    )
    (net (code "28") (name "DPLL_VDD_DIA_B") (class "Default")
      (node (ref "C92") (pin "1") (pinfunction "1_1") (pintype "passive"))
      (node (ref "C93") (pin "1") (pinfunction "1_1") (pintype "passive"))
      (node (ref "L4") (pin "2") (pinfunction "2_2") (pintype "passive"))
    )
    (net (code "29") (name "DPLL_VDD_DIG") (class "Default")
      (node (ref "C79") (pin "1") (pinfunction "1_1") (pintype "passive"))
      (node (ref "C80") (pin "1") (pinfunction "1_1") (pintype "passive"))
      (node (ref "C81") (pin "1") (pinfunction "1_1") (pintype "passive"))
      (node (ref "C82") (pin "1") (pinfunction "1_1") (pintype "passive"))
      (node (ref "R79") (pin "2") (pinfunction "2_2") (pintype "passive"))
    )
    (net (code "30") (name "DPLL_VDD_GPIO") (class "Default")
      (node (ref "C95") (pin "1") (pinfunction "1_1") (pintype "passive"))
      (node (ref "C96") (pin "1") (pinfunction "1_1") (pintype "passive"))
      (node (ref "C97") (pin "1") (pinfunction "1_1") (pintype "passive"))
      (node (ref "C98") (pin "1") (pinfunction "1_1") (pintype "passive"))
      (node (ref "R80") (pin "2") (pinfunction "2_2") (pintype "passive"))
    )
    (net (code "31") (name "DPLL_XO") (class "Default")
      (node (ref "R62") (pin "1") (pinfunction "1_1") (pintype "passive"))
      (node (ref "R81") (pin "1") (pinfunction "1_1") (pintype "passive"))
    )
    (net (code "32") (name "GND") (class "Default")
      (node (ref "C100") (pin "2") (pinfunction "2_2") (pintype "passive"))
      (node (ref "C101") (pin "2") (pinfunction "2_2") (pintype "passive"))
      (node (ref "C102") (pin "2") (pinfunction "2_2") (pintype "passive"))
      (node (ref "C103") (pin "2") (pinfunction "2_2") (pintype "passive"))
      (node (ref "C104") (pin "2") (pinfunction "2_2") (pintype "passive"))
      (node (ref "C105") (pin "2") (pinfunction "2_2") (pintype "passive"))
      (node (ref "C106") (pin "2") (pinfunction "2_2") (pintype "passive"))
      (node (ref "C107") (pin "2") (pinfunction "2_2") (pintype "passive"))
      (node (ref "C108") (pin "2") (pinfunction "2_2") (pintype "passive"))
      (node (ref "C109") (pin "2") (pinfunction "2_2") (pintype "passive"))
      (node (ref "C110") (pin "2") (pinfunction "2_2") (pintype "passive"))
      (node (ref "C111") (pin "2") (pinfunction "2_2") (pintype "passive"))
      (node (ref "C112") (pin "2") (pinfunction "2_2") (pintype "passive"))
      (node (ref "C113") (pin "2") (pinfunction "2_2") (pintype "passive"))
      (node (ref "C114") (pin "2") (pinfunction "2_2") (pintype "passive"))
      (node (ref "C115") (pin "2") (pinfunction "2_2") (pintype "passive"))
      (node (ref "C116") (pin "2") (pinfunction "2_2") (pintype "passive"))
      (node (ref "C117") (pin "2") (pinfunction "2_2") (pintype "passive"))
      (node (ref "C118") (pin "2") (pinfunction "2_2") (pintype "passive"))
      (node (ref "C119") (pin "2") (pinfunction "2_2") (pintype "passive"))
      (node (ref "C120") (pin "2") (pinfunction "2_2") (pintype "passive"))
      (node (ref "C121") (pin "2") (pinfunction "2_2") (pintype "passive"))
      (node (ref "C122") (pin "2") (pinfunction "2_2") (pintype "passive"))
      (node (ref "C123") (pin "2") (pinfunction "2_2") (pintype "passive"))
      (node (ref "C124") (pin "2") (pinfunction "2_2") (pintype "passive"))
      (node (ref "C125") (pin "2") (pinfunction "2_2") (pintype "passive"))
      (node (ref "C126") (pin "2") (pinfunction "2_2") (pintype "passive"))
      (node (ref "C127") (pin "2") (pinfunction "2_2") (pintype "passive"))
      (node (ref "C128") (pin "2") (pinfunction "2_2") (pintype "passive"))
      (node (ref "C129") (pin "2") (pinfunction "2_2") (pintype "passive"))
      (node (ref "C130") (pin "2") (pinfunction "2_2") (pintype "passive"))
      (node (ref "C131") (pin "2") (pinfunction "2_2") (pintype "passive"))
      (node (ref "C132") (pin "2") (pinfunction "2_2") (pintype "passive"))
      (node (ref "C133") (pin "2") (pinfunction "2_2") (pintype "passive"))
      (node (ref "C134") (pin "2") (pinfunction "2_2") (pintype "passive"))
      (node (ref "C135") (pin "2") (pinfunction "2_2") (pintype "passive"))
      (node (ref "C136") (pin "2") (pinfunction "2_2") (pintype "passive"))
      (node (ref "C137") (pin "2") (pinfunction "2_2") (pintype "passive"))
      (node (ref "C138") (pin "2") (pinfunction "2_2") (pintype "passive"))
      (node (ref "C139") (pin "2") (pinfunction "2_2") (pintype "passive"))
      (node (ref "C140") (pin "2") (pinfunction "2_2") (pintype "passive"))
      (node (ref "C141") (pin "2") (pinfunction "2_2") (pintype "passive"))
      (node (ref "C142") (pin "2") (pinfunction "2_2") (pintype "passive"))
      (node (ref "C143") (pin "2") (pinfunction "2_2") (pintype "passive"))
      (node (ref "C144") (pin "2") (pinfunction "2_2") (pintype "passive"))
      (node (ref "C145") (pin "1") (pinfunction "1_1") (pintype "passive"))
      (node (ref "C146") (pin "2") (pinfunction "2_2") (pintype "passive"))
      (node (ref "C147") (pin "2") (pinfunction "2_2") (pintype "passive"))
      (node (ref "C148") (pin "2") (pinfunction "2_2") (pintype "passive"))
      (node (ref "C149") (pin "2") (pinfunction "2_2") (pintype "passive"))
      (node (ref "C150") (pin "2") (pinfunction "2_2") (pintype "passive"))
      (node (ref "C151") (pin "1") (pinfunction "1_1") (pintype "passive"))
      (node (ref "C153") (pin "2") (pinfunction "2_2") (pintype "passive"))
      (node (ref "C154") (pin "2") (pinfunction "2_2") (pintype "passive"))
      (node (ref "C155") (pin "2") (pinfunction "2_2") (pintype "passive"))
      (node (ref "C156") (pin "2") (pinfunction "2_2") (pintype "passive"))
      (node (ref "C242") (pin "2") (pinfunction "2_2") (pintype "passive"))
      (node (ref "C243") (pin "2") (pinfunction "2_2") (pintype "passive"))
      (node (ref "C244") (pin "2") (pinfunction "2_2") (pintype "passive"))
      (node (ref "C245") (pin "2") (pinfunction "2_2") (pintype "passive"))
      (node (ref "C246") (pin "2") (pinfunction "2_2") (pintype "passive"))
      (node (ref "C247") (pin "2") (pinfunction "2_2") (pintype "passive"))
      (node (ref "C248") (pin "2") (pinfunction "2_2") (pintype "passive"))
      (node (ref "C249") (pin "2") (pinfunction "2_2") (pintype "passive"))
      (node (ref "C250") (pin "2") (pinfunction "2_2") (pintype "passive"))
      (node (ref "C251") (pin "2") (pinfunction "2_2") (pintype "passive"))
      (node (ref "C252") (pin "2") (pinfunction "2_2") (pintype "passive"))
      (node (ref "C253") (pin "2") (pinfunction "2_2") (pintype "passive"))
      (node (ref "C254") (pin "2") (pinfunction "2_2") (pintype "passive"))
      (node (ref "C255") (pin "2") (pinfunction "2_2") (pintype "passive"))
      (node (ref "C256") (pin "2") (pinfunction "2_2") (pintype "passive"))
      (node (ref "C257") (pin "2") (pinfunction "2_2") (pintype "passive"))
      (node (ref "C258") (pin "2") (pinfunction "2_2") (pintype "passive"))
      (node (ref "C259") (pin "2") (pinfunction "2_2") (pintype "passive"))
      (node (ref "C260") (pin "2") (pinfunction "2_2") (pintype "passive"))
      (node (ref "C261") (pin "2") (pinfunction "2_2") (pintype "passive"))
      (node (ref "C262") (pin "2") (pinfunction "2_2") (pintype "passive"))
      (node (ref "C263") (pin "2") (pinfunction "2_2") (pintype "passive"))
      (node (ref "C264") (pin "2") (pinfunction "2_2") (pintype "passive"))
      (node (ref "C265") (pin "2") (pinfunction "2_2") (pintype "passive"))
      (node (ref "C266") (pin "2") (pinfunction "2_2") (pintype "passive"))
      (node (ref "C267") (pin "2") (pinfunction "2_2") (pintype "passive"))
      (node (ref "C268") (pin "2") (pinfunction "2_2") (pintype "passive"))
      (node (ref "C269") (pin "2") (pinfunction "2_2") (pintype "passive"))
      (node (ref "C270") (pin "2") (pinfunction "2_2") (pintype "passive"))
      (node (ref "C271") (pin "2") (pinfunction "2_2") (pintype "passive"))
      (node (ref "C272") (pin "2") (pinfunction "2_2") (pintype "passive"))
      (node (ref "C273") (pin "2") (pinfunction "2_2") (pintype "passive"))
      (node (ref "C274") (pin "2") (pinfunction "2_2") (pintype "passive"))
      (node (ref "C275") (pin "2") (pinfunction "2_2") (pintype "passive"))
      (node (ref "C276") (pin "2") (pinfunction "2_2") (pintype "passive"))
      (node (ref "C277") (pin "2") (pinfunction "2_2") (pintype "passive"))
      (node (ref "C281") (pin "2") (pinfunction "2_2") (pintype "passive"))
      (node (ref "C282") (pin "2") (pinfunction "2_2") (pintype "passive"))
      (node (ref "C77") (pin "2") (pinfunction "2_2") (pintype "passive"))
      (node (ref "C78") (pin "2") (pinfunction "2_2") (pintype "passive"))
      (node (ref "C79") (pin "2") (pinfunction "2_2") (pintype "passive"))
      (node (ref "C80") (pin "2") (pinfunction "2_2") (pintype "passive"))
      (node (ref "C81") (pin "2") (pinfunction "2_2") (pintype "passive"))
      (node (ref "C82") (pin "2") (pinfunction "2_2") (pintype "passive"))
      (node (ref "C83") (pin "2") (pinfunction "2_2") (pintype "passive"))
      (node (ref "C84") (pin "2") (pinfunction "2_2") (pintype "passive"))
      (node (ref "C85") (pin "2") (pinfunction "2_2") (pintype "passive"))
      (node (ref "C86") (pin "2") (pinfunction "2_2") (pintype "passive"))
      (node (ref "C87") (pin "2") (pinfunction "2_2") (pintype "passive"))
      (node (ref "C88") (pin "2") (pinfunction "2_2") (pintype "passive"))
      (node (ref "C89") (pin "2") (pinfunction "2_2") (pintype "passive"))
      (node (ref "C90") (pin "2") (pinfunction "2_2") (pintype "passive"))
      (node (ref "C91") (pin "2") (pinfunction "2_2") (pintype "passive"))
      (node (ref "C92") (pin "2") (pinfunction "2_2") (pintype "passive"))
      (node (ref "C93") (pin "2") (pinfunction "2_2") (pintype "passive"))
      (node (ref "C94") (pin "2") (pinfunction "2_2") (pintype "passive"))
      (node (ref "C95") (pin "2") (pinfunction "2_2") (pintype "passive"))
      (node (ref "C96") (pin "2") (pinfunction "2_2") (pintype "passive"))
      (node (ref "C97") (pin "2") (pinfunction "2_2") (pintype "passive"))
      (node (ref "C98") (pin "2") (pinfunction "2_2") (pintype "passive"))
      (node (ref "C99") (pin "2") (pinfunction "2_2") (pintype "passive"))
      (node (ref "R212") (pin "1") (pinfunction "1_1") (pintype "passive"))
      (node (ref "R89") (pin "1") (pinfunction "1_1") (pintype "passive"))
      (node (ref "Y2") (pin "5") (pinfunction "GND_5") (pintype "power_in"))
      (node (ref "Y3") (pin "3") (pinfunction "GND_3") (pintype "power_in"))
      (node (ref "Y4") (pin "2") (pinfunction "GND_2") (pintype "power_in"))
      (node (ref "Y6") (pin "1") (pinfunction "GND/NC_1") (pintype "passive"))
      (node (ref "Y6") (pin "2") (pinfunction "GND_2") (pintype "power_in"))
    )
    (net (code "33") (name "Net-(C152-Pad1)") (class "Default")
      (node (ref "C152") (pin "1") (pinfunction "1_1") (pintype "passive"))
      (node (ref "R87") (pin "1") (pinfunction "1_1") (pintype "passive"))
      (node (ref "R88") (pin "2") (pinfunction "2_2") (pintype "passive"))
      (node (ref "R89") (pin "2") (pinfunction "2_2") (pintype "passive"))
    )
    (net (code "34") (name "Net-(C278-Pad1)") (class "Default")
      (node (ref "C278") (pin "1") (pinfunction "1_1") (pintype "passive"))
      (node (ref "R210") (pin "1") (pinfunction "1_1") (pintype "passive"))
      (node (ref "R211") (pin "2") (pinfunction "2_2") (pintype "passive"))
      (node (ref "R212") (pin "2") (pinfunction "2_2") (pintype "passive"))
    )
    (net (code "35") (name "Net-(R83-Pad1)") (class "Default")
      (node (ref "R83") (pin "1") (pinfunction "1_1") (pintype "passive"))
      (node (ref "Y2") (pin "7") (pinfunction "NC_7") (pintype "passive"))
    )
    (net (code "36") (name "Net-(R84-Pad1)") (class "Default")
      (node (ref "R84") (pin "1") (pinfunction "1_1") (pintype "passive"))
      (node (ref "Y2") (pin "8") (pinfunction "NC_8") (pintype "passive"))
    )
    (net (code "37") (name "Net-(Y2-CLK)") (class "Default")
      (node (ref "R81") (pin "2") (pinfunction "2_2") (pintype "passive"))
      (node (ref "Y2") (pin "6") (pinfunction "CLK_6") (pintype "output"))
    )
    (net (code "38") (name "Net-(Y2-OE)") (class "Default")
      (node (ref "R82") (pin "2") (pinfunction "2_2") (pintype "passive"))
      (node (ref "Y2") (pin "1") (pinfunction "OE_1") (pintype "input"))
    )
    (net (code "39") (name "Net-(Y2-VDD)") (class "Default")
      (node (ref "C150") (pin "1") (pinfunction "1_1") (pintype "passive"))
      (node (ref "C151") (pin "2") (pinfunction "2_2") (pintype "passive"))
      (node (ref "FB5") (pin "1") (pinfunction "1_1") (pintype "passive"))
      (node (ref "R82") (pin "1") (pinfunction "1_1") (pintype "passive"))
      (node (ref "Y2") (pin "10") (pinfunction "VDD_10") (pintype "power_in"))
      (node (ref "Y6") (pin "4") (pinfunction "VDD_4") (pintype "power_in"))
    )
    (net (code "40") (name "Net-(Y3-Output)") (class "Default")
      (node (ref "R88") (pin "1") (pinfunction "1_1") (pintype "passive"))
      (node (ref "Y3") (pin "4") (pinfunction "Output_4") (pintype "output"))
    )
    (net (code "41") (name "Net-(Y3-VDD)") (class "Default")
      (node (ref "C155") (pin "1") (pinfunction "1_1") (pintype "passive"))
      (node (ref "C156") (pin "1") (pinfunction "1_1") (pintype "passive"))
      (node (ref "C281") (pin "1") (pinfunction "1_1") (pintype "passive"))
      (node (ref "C282") (pin "1") (pinfunction "1_1") (pintype "passive"))
      (node (ref "L19") (pin "2") (pinfunction "2_2") (pintype "passive"))
      (node (ref "Y3") (pin "1") (pinfunction "~{Tri-State}_1") (pintype "input"))
      (node (ref "Y3") (pin "6") (pinfunction "VDD_6") (pintype "power_in"))
      (node (ref "Y4") (pin "4") (pinfunction "VDD_4") (pintype "power_in"))
    )
    (net (code "42") (name "Net-(Y4-OUT)") (class "Default")
      (node (ref "R211") (pin "1") (pinfunction "1_1") (pintype "passive"))
      (node (ref "Y4") (pin "3") (pinfunction "OUT_3") (pintype "output"))
    )
    (net (code "43") (name "Net-(Y6-OUTPUT)") (class "Default")
      (node (ref "R62") (pin "2") (pinfunction "2_2") (pintype "passive"))
      (node (ref "Y6") (pin "3") (pinfunction "OUTPUT_3") (pintype "output"))
    )
    (net (code "44") (name "P1V8") (class "Default")
      (node (ref "C108") (pin "1") (pinfunction "1_1") (pintype "passive"))
      (node (ref "C115") (pin "1") (pinfunction "1_1") (pintype "passive"))
      (node (ref "C129") (pin "1") (pinfunction "1_1") (pintype "passive"))
      (node (ref "C244") (pin "1") (pinfunction "1_1") (pintype "passive"))
      (node (ref "C245") (pin "1") (pinfunction "1_1") (pintype "passive"))
      (node (ref "C246") (pin "1") (pinfunction "1_1") (pintype "passive"))
      (node (ref "C249") (pin "1") (pinfunction "1_1") (pintype "passive"))
      (node (ref "C252") (pin "1") (pinfunction "1_1") (pintype "passive"))
      (node (ref "C255") (pin "1") (pinfunction "1_1") (pintype "passive"))
      (node (ref "C258") (pin "1") (pinfunction "1_1") (pintype "passive"))
      (node (ref "C261") (pin "1") (pinfunction "1_1") (pintype "passive"))
      (node (ref "C88") (pin "1") (pinfunction "1_1") (pintype "passive"))
      (node (ref "C89") (pin "1") (pinfunction "1_1") (pintype "passive"))
      (node (ref "C90") (pin "1") (pinfunction "1_1") (pintype "passive"))
      (node (ref "C94") (pin "1") (pinfunction "1_1") (pintype "passive"))
      (node (ref "L13") (pin "1") (pinfunction "1_1") (pintype "passive"))
      (node (ref "L21") (pin "1") (pinfunction "1_1") (pintype "passive"))
      (node (ref "L22") (pin "1") (pinfunction "1_1") (pintype "passive"))
      (node (ref "L23") (pin "1") (pinfunction "1_1") (pintype "passive"))
      (node (ref "L24") (pin "1") (pinfunction "1_1") (pintype "passive"))
      (node (ref "L25") (pin "1") (pinfunction "1_1") (pintype "passive"))
      (node (ref "L26") (pin "1") (pinfunction "1_1") (pintype "passive"))
      (node (ref "L3") (pin "1") (pinfunction "1_1") (pintype "passive"))
      (node (ref "L4") (pin "1") (pinfunction "1_1") (pintype "passive"))
      (node (ref "L6") (pin "1") (pinfunction "1_1") (pintype "passive"))
      (node (ref "L9") (pin "1") (pinfunction "1_1") (pintype "passive"))
      (node (ref "R79") (pin "1") (pinfunction "1_1") (pintype "passive"))
    )
    (net (code "45") (name "P3V3") (class "Default")
      (node (ref "C101") (pin "1") (pinfunction "1_1") (pintype "passive"))
      (node (ref "C104") (pin "1") (pinfunction "1_1") (pintype "passive"))
      (node (ref "C105") (pin "1") (pinfunction "1_1") (pintype "passive"))
      (node (ref "C109") (pin "1") (pinfunction "1_1") (pintype "passive"))
      (node (ref "C110") (pin "1") (pinfunction "1_1") (pintype "passive"))
      (node (ref "C116") (pin "1") (pinfunction "1_1") (pintype "passive"))
      (node (ref "C117") (pin "1") (pinfunction "1_1") (pintype "passive"))
      (node (ref "C122") (pin "1") (pinfunction "1_1") (pintype "passive"))
      (node (ref "C123") (pin "1") (pinfunction "1_1") (pintype "passive"))
      (node (ref "C124") (pin "1") (pinfunction "1_1") (pintype "passive"))
      (node (ref "C130") (pin "1") (pinfunction "1_1") (pintype "passive"))
      (node (ref "C131") (pin "1") (pinfunction "1_1") (pintype "passive"))
      (node (ref "C136") (pin "1") (pinfunction "1_1") (pintype "passive"))
      (node (ref "C137") (pin "1") (pinfunction "1_1") (pintype "passive"))
      (node (ref "C138") (pin "1") (pinfunction "1_1") (pintype "passive"))
      (node (ref "C141") (pin "1") (pinfunction "1_1") (pintype "passive"))
      (node (ref "C142") (pin "1") (pinfunction "1_1") (pintype "passive"))
      (node (ref "C145") (pin "2") (pinfunction "2_2") (pintype "passive"))
      (node (ref "C146") (pin "1") (pinfunction "1_1") (pintype "passive"))
      (node (ref "C147") (pin "1") (pinfunction "1_1") (pintype "passive"))
      (node (ref "C153") (pin "1") (pinfunction "1_1") (pintype "passive"))
      (node (ref "C154") (pin "1") (pinfunction "1_1") (pintype "passive"))
      (node (ref "C262") (pin "1") (pinfunction "1_1") (pintype "passive"))
      (node (ref "C263") (pin "1") (pinfunction "1_1") (pintype "passive"))
      (node (ref "C266") (pin "1") (pinfunction "1_1") (pintype "passive"))
      (node (ref "C267") (pin "1") (pinfunction "1_1") (pintype "passive"))
      (node (ref "C270") (pin "1") (pinfunction "1_1") (pintype "passive"))
      (node (ref "C271") (pin "1") (pinfunction "1_1") (pintype "passive"))
      (node (ref "C272") (pin "1") (pinfunction "1_1") (pintype "passive"))
      (node (ref "C273") (pin "1") (pinfunction "1_1") (pintype "passive"))
      (node (ref "C86") (pin "1") (pinfunction "1_1") (pintype "passive"))
      (node (ref "C87") (pin "1") (pinfunction "1_1") (pintype "passive"))
      (node (ref "C91") (pin "1") (pinfunction "1_1") (pintype "passive"))
      (node (ref "FB5") (pin "2") (pinfunction "2_2") (pintype "passive"))
      (node (ref "L10") (pin "1") (pinfunction "1_1") (pintype "passive"))
      (node (ref "L11") (pin "1") (pinfunction "1_1") (pintype "passive"))
      (node (ref "L12") (pin "1") (pinfunction "1_1") (pintype "passive"))
      (node (ref "L14") (pin "1") (pinfunction "1_1") (pintype "passive"))
      (node (ref "L15") (pin "1") (pinfunction "1_1") (pintype "passive"))
      (node (ref "L16") (pin "1") (pinfunction "1_1") (pintype "passive"))
      (node (ref "L17") (pin "1") (pinfunction "1_1") (pintype "passive"))
      (node (ref "L18") (pin "1") (pinfunction "1_1") (pintype "passive"))
      (node (ref "L19") (pin "1") (pinfunction "1_1") (pintype "passive"))
      (node (ref "L2") (pin "1") (pinfunction "1_1") (pintype "passive"))
      (node (ref "L27") (pin "1") (pinfunction "1_1") (pintype "passive"))
      (node (ref "L28") (pin "1") (pinfunction "1_1") (pintype "passive"))
      (node (ref "L29") (pin "1") (pinfunction "1_1") (pintype "passive"))
      (node (ref "L30") (pin "1") (pinfunction "1_1") (pintype "passive"))
      (node (ref "L5") (pin "1") (pinfunction "1_1") (pintype "passive"))
      (node (ref "L7") (pin "1") (pinfunction "1_1") (pintype "passive"))
      (node (ref "L8") (pin "1") (pinfunction "1_1") (pintype "passive"))
      (node (ref "R210") (pin "2") (pinfunction "2_2") (pintype "passive"))
      (node (ref "R80") (pin "1") (pinfunction "1_1") (pintype "passive"))
      (node (ref "R83") (pin "2") (pinfunction "2_2") (pintype "passive"))
      (node (ref "R84") (pin "2") (pinfunction "2_2") (pintype "passive"))
      (node (ref "R87") (pin "2") (pinfunction "2_2") (pintype "passive"))
    )
    (net (code "46") (name "TOP_SENS_I2C_SCL") (class "Default")
      (node (ref "Y2") (pin "3") (pinfunction "NC_3") (pintype "passive"))
    )
    (net (code "47") (name "TOP_SENS_I2C_SDA") (class "Default")
      (node (ref "Y2") (pin "2") (pinfunction "NC_2") (pintype "passive"))
    )
    (net (code "48") (name "unconnected-(Y2-NC-Pad4)") (class "Default")
      (node (ref "Y2") (pin "4") (pinfunction "NC_4") (pintype "passive"))
    )
    (net (code "49") (name "unconnected-(Y2-NC-Pad9)") (class "Default")
      (node (ref "Y2") (pin "9") (pinfunction "NC_9") (pintype "passive"))
    )
    (net (code "50") (name "unconnected-(Y4-NC-Pad1)") (class "Default")
      (node (ref "Y4") (pin "1") (pinfunction "NC_1") (pintype "passive"))
    )
  )
)
